# audiobackboard.net
KiCad netlist of a schematic drawn in EasyEDA
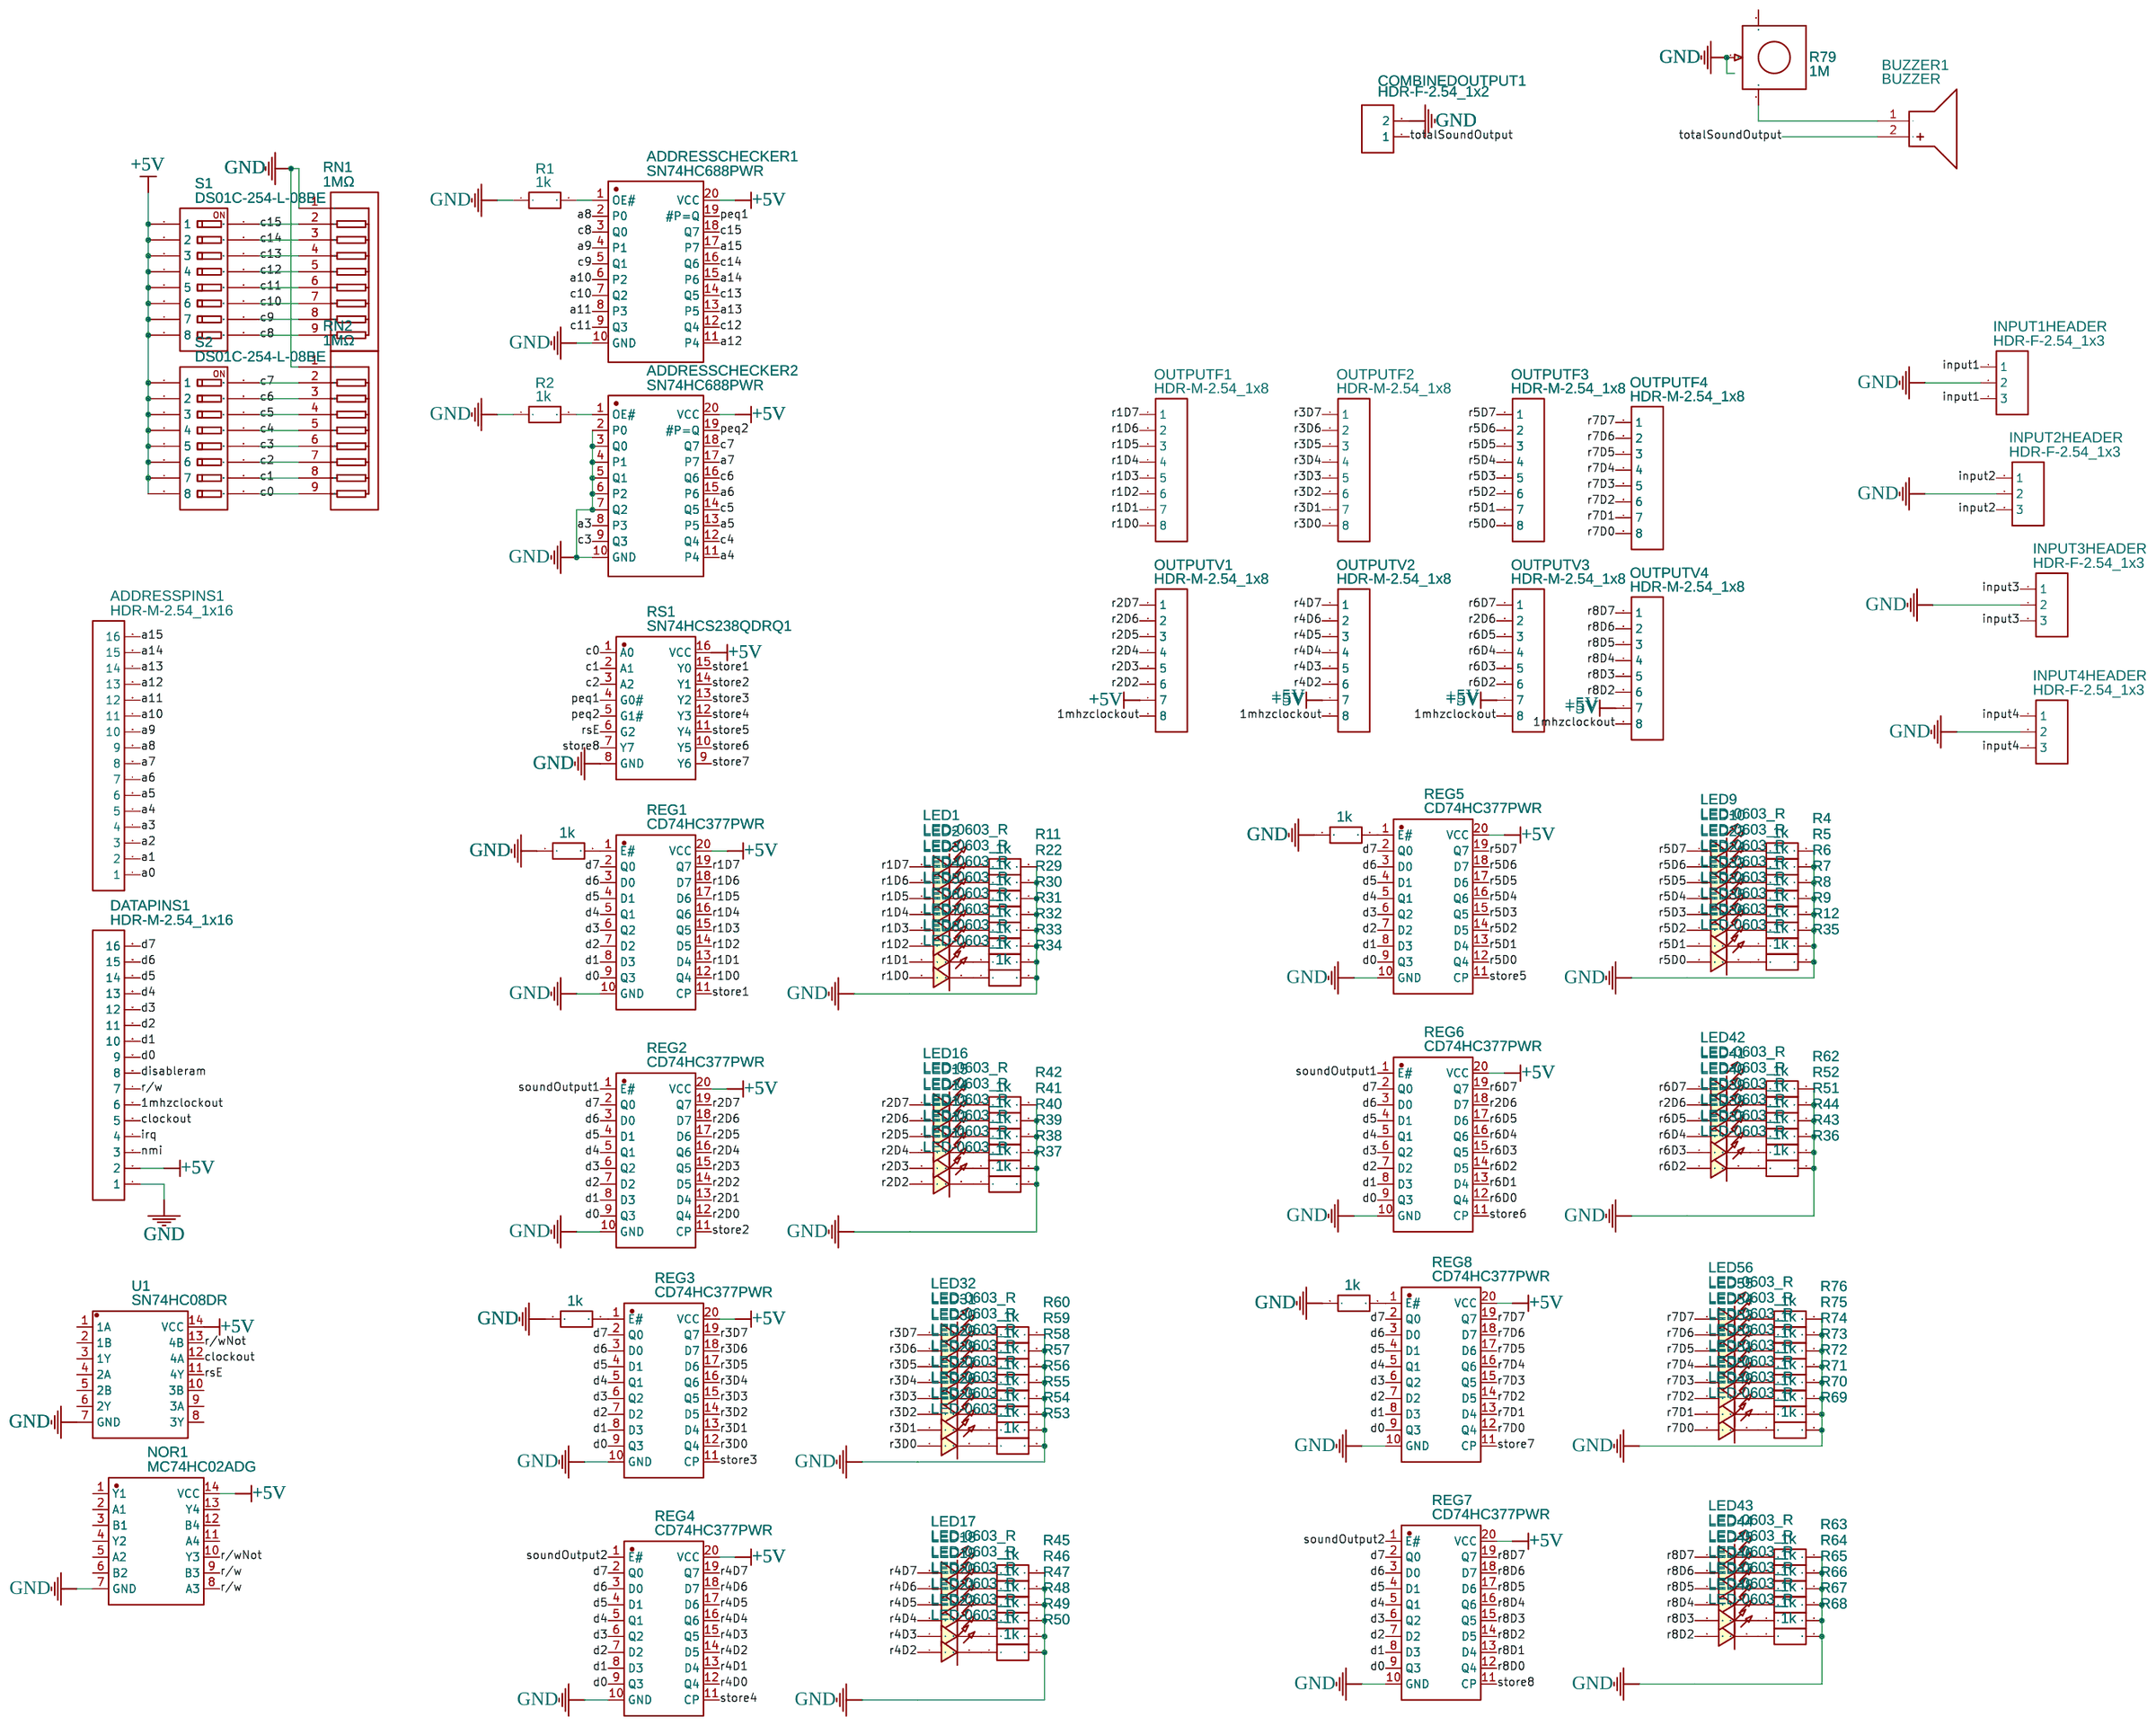
[diagram p0: schematic sheet]

(export (version "E")
  (design (tool "Eeschema 10.0.6"))
  (components
    (comp (ref "ADDRESSCHECKER1")
      (value "SN74HC688PWR")
      (fields (field (name "Manufacturer") "TI(德州仪器)"))
      (libsource (lib "") (part "SN74HC688PWR"))
    )
    (comp (ref "ADDRESSCHECKER2")
      (value "SN74HC688PWR")
      (fields (field (name "Manufacturer") "TI(德州仪器)"))
      (libsource (lib "") (part "SN74HC688PWR"))
    )
    (comp (ref "ADDRESSPINS1") (value "HDR-M-2.54_1x16") (libsource (lib "") (part "HDR-M-2.54_1x16_1")))
    (comp (ref "BUZZER1")
      (value "BUZZER")
      (fields (field (name "Manufacturer Part") "buzzer"))
      (libsource (lib "") (part "BUZZER"))
    )
    (comp (ref "COMBINEDOUTPUT1") (value "HDR-F-2.54_1x2") (libsource (lib "") (part "HDR-F-2.54_1x2")))
    (comp (ref "DATAPINS1") (value "HDR-M-2.54_1x16") (libsource (lib "") (part "HDR-M-2.54_1x16")))
    (comp (ref "INPUT1HEADER") (value "HDR-F-2.54_1x3") (libsource (lib "") (part "HDR-F-2.54_1x3")))
    (comp (ref "INPUT2HEADER") (value "HDR-F-2.54_1x3") (libsource (lib "") (part "HDR-F-2.54_1x3_2")))
    (comp (ref "INPUT3HEADER") (value "HDR-F-2.54_1x3") (libsource (lib "") (part "HDR-F-2.54_1x3_3")))
    (comp (ref "INPUT4HEADER") (value "HDR-F-2.54_1x3") (libsource (lib "") (part "HDR-F-2.54_1x3_1")))
    (comp (ref "LED1")
      (value "LED-0603_R")
      (fields
        (field (name "Manufacturer Part") "19-217/R6C-AL1M2VY/3T")
        (field (name "Manufacturer") "EVERLIGHT(台湾亿光)")
      )
      (libsource (lib "") (part "LED-0603_R"))
    )
    (comp (ref "LED2")
      (value "LED-0603_R")
      (fields
        (field (name "Manufacturer Part") "19-217/R6C-AL1M2VY/3T")
        (field (name "Manufacturer") "EVERLIGHT(台湾亿光)")
      )
      (libsource (lib "") (part "LED-0603_R"))
    )
    (comp (ref "LED3")
      (value "LED-0603_R")
      (fields
        (field (name "Manufacturer Part") "19-217/R6C-AL1M2VY/3T")
        (field (name "Manufacturer") "EVERLIGHT(台湾亿光)")
      )
      (libsource (lib "") (part "LED-0603_R"))
    )
    (comp (ref "LED4")
      (value "LED-0603_R")
      (fields
        (field (name "Manufacturer Part") "19-217/R6C-AL1M2VY/3T")
        (field (name "Manufacturer") "EVERLIGHT(台湾亿光)")
      )
      (libsource (lib "") (part "LED-0603_R"))
    )
    (comp (ref "LED5")
      (value "LED-0603_R")
      (fields
        (field (name "Manufacturer Part") "19-217/R6C-AL1M2VY/3T")
        (field (name "Manufacturer") "EVERLIGHT(台湾亿光)")
      )
      (libsource (lib "") (part "LED-0603_R"))
    )
    (comp (ref "LED6")
      (value "LED-0603_R")
      (fields
        (field (name "Manufacturer Part") "19-217/R6C-AL1M2VY/3T")
        (field (name "Manufacturer") "EVERLIGHT(台湾亿光)")
      )
      (libsource (lib "") (part "LED-0603_R"))
    )
    (comp (ref "LED7")
      (value "LED-0603_R")
      (fields
        (field (name "Manufacturer Part") "19-217/R6C-AL1M2VY/3T")
        (field (name "Manufacturer") "EVERLIGHT(台湾亿光)")
      )
      (libsource (lib "") (part "LED-0603_R"))
    )
    (comp (ref "LED8")
      (value "LED-0603_R")
      (fields
        (field (name "Manufacturer Part") "19-217/R6C-AL1M2VY/3T")
        (field (name "Manufacturer") "EVERLIGHT(台湾亿光)")
      )
      (libsource (lib "") (part "LED-0603_R"))
    )
    (comp (ref "LED9")
      (value "LED-0603_R")
      (fields
        (field (name "Manufacturer Part") "19-217/R6C-AL1M2VY/3T")
        (field (name "Manufacturer") "EVERLIGHT(台湾亿光)")
      )
      (libsource (lib "") (part "LED-0603_R"))
    )
    (comp (ref "LED10")
      (value "LED-0603_R")
      (fields
        (field (name "Manufacturer Part") "19-217/R6C-AL1M2VY/3T")
        (field (name "Manufacturer") "EVERLIGHT(台湾亿光)")
      )
      (libsource (lib "") (part "LED-0603_R"))
    )
    (comp (ref "LED11")
      (value "LED-0603_R")
      (fields
        (field (name "Manufacturer Part") "19-217/R6C-AL1M2VY/3T")
        (field (name "Manufacturer") "EVERLIGHT(台湾亿光)")
      )
      (libsource (lib "") (part "LED-0603_R"))
    )
    (comp (ref "LED12")
      (value "LED-0603_R")
      (fields
        (field (name "Manufacturer Part") "19-217/R6C-AL1M2VY/3T")
        (field (name "Manufacturer") "EVERLIGHT(台湾亿光)")
      )
      (libsource (lib "") (part "LED-0603_R"))
    )
    (comp (ref "LED13")
      (value "LED-0603_R")
      (fields
        (field (name "Manufacturer Part") "19-217/R6C-AL1M2VY/3T")
        (field (name "Manufacturer") "EVERLIGHT(台湾亿光)")
      )
      (libsource (lib "") (part "LED-0603_R"))
    )
    (comp (ref "LED14")
      (value "LED-0603_R")
      (fields
        (field (name "Manufacturer Part") "19-217/R6C-AL1M2VY/3T")
        (field (name "Manufacturer") "EVERLIGHT(台湾亿光)")
      )
      (libsource (lib "") (part "LED-0603_R"))
    )
    (comp (ref "LED15")
      (value "LED-0603_R")
      (fields
        (field (name "Manufacturer Part") "19-217/R6C-AL1M2VY/3T")
        (field (name "Manufacturer") "EVERLIGHT(台湾亿光)")
      )
      (libsource (lib "") (part "LED-0603_R"))
    )
    (comp (ref "LED16")
      (value "LED-0603_R")
      (fields
        (field (name "Manufacturer Part") "19-217/R6C-AL1M2VY/3T")
        (field (name "Manufacturer") "EVERLIGHT(台湾亿光)")
      )
      (libsource (lib "") (part "LED-0603_R"))
    )
    (comp (ref "LED17")
      (value "LED-0603_R")
      (fields
        (field (name "Manufacturer Part") "19-217/R6C-AL1M2VY/3T")
        (field (name "Manufacturer") "EVERLIGHT(台湾亿光)")
      )
      (libsource (lib "") (part "LED-0603_R"))
    )
    (comp (ref "LED18")
      (value "LED-0603_R")
      (fields
        (field (name "Manufacturer Part") "19-217/R6C-AL1M2VY/3T")
        (field (name "Manufacturer") "EVERLIGHT(台湾亿光)")
      )
      (libsource (lib "") (part "LED-0603_R"))
    )
    (comp (ref "LED19")
      (value "LED-0603_R")
      (fields
        (field (name "Manufacturer Part") "19-217/R6C-AL1M2VY/3T")
        (field (name "Manufacturer") "EVERLIGHT(台湾亿光)")
      )
      (libsource (lib "") (part "LED-0603_R"))
    )
    (comp (ref "LED20")
      (value "LED-0603_R")
      (fields
        (field (name "Manufacturer Part") "19-217/R6C-AL1M2VY/3T")
        (field (name "Manufacturer") "EVERLIGHT(台湾亿光)")
      )
      (libsource (lib "") (part "LED-0603_R"))
    )
    (comp (ref "LED21")
      (value "LED-0603_R")
      (fields
        (field (name "Manufacturer Part") "19-217/R6C-AL1M2VY/3T")
        (field (name "Manufacturer") "EVERLIGHT(台湾亿光)")
      )
      (libsource (lib "") (part "LED-0603_R"))
    )
    (comp (ref "LED22")
      (value "LED-0603_R")
      (fields
        (field (name "Manufacturer Part") "19-217/R6C-AL1M2VY/3T")
        (field (name "Manufacturer") "EVERLIGHT(台湾亿光)")
      )
      (libsource (lib "") (part "LED-0603_R"))
    )
    (comp (ref "LED23")
      (value "LED-0603_R")
      (fields
        (field (name "Manufacturer Part") "19-217/R6C-AL1M2VY/3T")
        (field (name "Manufacturer") "EVERLIGHT(台湾亿光)")
      )
      (libsource (lib "") (part "LED-0603_R"))
    )
    (comp (ref "LED24")
      (value "LED-0603_R")
      (fields
        (field (name "Manufacturer Part") "19-217/R6C-AL1M2VY/3T")
        (field (name "Manufacturer") "EVERLIGHT(台湾亿光)")
      )
      (libsource (lib "") (part "LED-0603_R"))
    )
    (comp (ref "LED25")
      (value "LED-0603_R")
      (fields
        (field (name "Manufacturer Part") "19-217/R6C-AL1M2VY/3T")
        (field (name "Manufacturer") "EVERLIGHT(台湾亿光)")
      )
      (libsource (lib "") (part "LED-0603_R"))
    )
    (comp (ref "LED26")
      (value "LED-0603_R")
      (fields
        (field (name "Manufacturer Part") "19-217/R6C-AL1M2VY/3T")
        (field (name "Manufacturer") "EVERLIGHT(台湾亿光)")
      )
      (libsource (lib "") (part "LED-0603_R"))
    )
    (comp (ref "LED27")
      (value "LED-0603_R")
      (fields
        (field (name "Manufacturer Part") "19-217/R6C-AL1M2VY/3T")
        (field (name "Manufacturer") "EVERLIGHT(台湾亿光)")
      )
      (libsource (lib "") (part "LED-0603_R"))
    )
    (comp (ref "LED28")
      (value "LED-0603_R")
      (fields
        (field (name "Manufacturer Part") "19-217/R6C-AL1M2VY/3T")
        (field (name "Manufacturer") "EVERLIGHT(台湾亿光)")
      )
      (libsource (lib "") (part "LED-0603_R"))
    )
    (comp (ref "LED29")
      (value "LED-0603_R")
      (fields
        (field (name "Manufacturer Part") "19-217/R6C-AL1M2VY/3T")
        (field (name "Manufacturer") "EVERLIGHT(台湾亿光)")
      )
      (libsource (lib "") (part "LED-0603_R"))
    )
    (comp (ref "LED30")
      (value "LED-0603_R")
      (fields
        (field (name "Manufacturer Part") "19-217/R6C-AL1M2VY/3T")
        (field (name "Manufacturer") "EVERLIGHT(台湾亿光)")
      )
      (libsource (lib "") (part "LED-0603_R"))
    )
    (comp (ref "LED31")
      (value "LED-0603_R")
      (fields
        (field (name "Manufacturer Part") "19-217/R6C-AL1M2VY/3T")
        (field (name "Manufacturer") "EVERLIGHT(台湾亿光)")
      )
      (libsource (lib "") (part "LED-0603_R"))
    )
    (comp (ref "LED32")
      (value "LED-0603_R")
      (fields
        (field (name "Manufacturer Part") "19-217/R6C-AL1M2VY/3T")
        (field (name "Manufacturer") "EVERLIGHT(台湾亿光)")
      )
      (libsource (lib "") (part "LED-0603_R"))
    )
    (comp (ref "LED33")
      (value "LED-0603_R")
      (fields
        (field (name "Manufacturer Part") "19-217/R6C-AL1M2VY/3T")
        (field (name "Manufacturer") "EVERLIGHT(台湾亿光)")
      )
      (libsource (lib "") (part "LED-0603_R"))
    )
    (comp (ref "LED34")
      (value "LED-0603_R")
      (fields
        (field (name "Manufacturer Part") "19-217/R6C-AL1M2VY/3T")
        (field (name "Manufacturer") "EVERLIGHT(台湾亿光)")
      )
      (libsource (lib "") (part "LED-0603_R"))
    )
    (comp (ref "LED35")
      (value "LED-0603_R")
      (fields
        (field (name "Manufacturer Part") "19-217/R6C-AL1M2VY/3T")
        (field (name "Manufacturer") "EVERLIGHT(台湾亿光)")
      )
      (libsource (lib "") (part "LED-0603_R"))
    )
    (comp (ref "LED36")
      (value "LED-0603_R")
      (fields
        (field (name "Manufacturer Part") "19-217/R6C-AL1M2VY/3T")
        (field (name "Manufacturer") "EVERLIGHT(台湾亿光)")
      )
      (libsource (lib "") (part "LED-0603_R"))
    )
    (comp (ref "LED37")
      (value "LED-0603_R")
      (fields
        (field (name "Manufacturer Part") "19-217/R6C-AL1M2VY/3T")
        (field (name "Manufacturer") "EVERLIGHT(台湾亿光)")
      )
      (libsource (lib "") (part "LED-0603_R"))
    )
    (comp (ref "LED38")
      (value "LED-0603_R")
      (fields
        (field (name "Manufacturer Part") "19-217/R6C-AL1M2VY/3T")
        (field (name "Manufacturer") "EVERLIGHT(台湾亿光)")
      )
      (libsource (lib "") (part "LED-0603_R"))
    )
    (comp (ref "LED39")
      (value "LED-0603_R")
      (fields
        (field (name "Manufacturer Part") "19-217/R6C-AL1M2VY/3T")
        (field (name "Manufacturer") "EVERLIGHT(台湾亿光)")
      )
      (libsource (lib "") (part "LED-0603_R"))
    )
    (comp (ref "LED40")
      (value "LED-0603_R")
      (fields
        (field (name "Manufacturer Part") "19-217/R6C-AL1M2VY/3T")
        (field (name "Manufacturer") "EVERLIGHT(台湾亿光)")
      )
      (libsource (lib "") (part "LED-0603_R"))
    )
    (comp (ref "LED41")
      (value "LED-0603_R")
      (fields
        (field (name "Manufacturer Part") "19-217/R6C-AL1M2VY/3T")
        (field (name "Manufacturer") "EVERLIGHT(台湾亿光)")
      )
      (libsource (lib "") (part "LED-0603_R"))
    )
    (comp (ref "LED42")
      (value "LED-0603_R")
      (fields
        (field (name "Manufacturer Part") "19-217/R6C-AL1M2VY/3T")
        (field (name "Manufacturer") "EVERLIGHT(台湾亿光)")
      )
      (libsource (lib "") (part "LED-0603_R"))
    )
    (comp (ref "LED43")
      (value "LED-0603_R")
      (fields
        (field (name "Manufacturer Part") "19-217/R6C-AL1M2VY/3T")
        (field (name "Manufacturer") "EVERLIGHT(台湾亿光)")
      )
      (libsource (lib "") (part "LED-0603_R"))
    )
    (comp (ref "LED44")
      (value "LED-0603_R")
      (fields
        (field (name "Manufacturer Part") "19-217/R6C-AL1M2VY/3T")
        (field (name "Manufacturer") "EVERLIGHT(台湾亿光)")
      )
      (libsource (lib "") (part "LED-0603_R"))
    )
    (comp (ref "LED45")
      (value "LED-0603_R")
      (fields
        (field (name "Manufacturer Part") "19-217/R6C-AL1M2VY/3T")
        (field (name "Manufacturer") "EVERLIGHT(台湾亿光)")
      )
      (libsource (lib "") (part "LED-0603_R"))
    )
    (comp (ref "LED46")
      (value "LED-0603_R")
      (fields
        (field (name "Manufacturer Part") "19-217/R6C-AL1M2VY/3T")
        (field (name "Manufacturer") "EVERLIGHT(台湾亿光)")
      )
      (libsource (lib "") (part "LED-0603_R"))
    )
    (comp (ref "LED47")
      (value "LED-0603_R")
      (fields
        (field (name "Manufacturer Part") "19-217/R6C-AL1M2VY/3T")
        (field (name "Manufacturer") "EVERLIGHT(台湾亿光)")
      )
      (libsource (lib "") (part "LED-0603_R"))
    )
    (comp (ref "LED48")
      (value "LED-0603_R")
      (fields
        (field (name "Manufacturer Part") "19-217/R6C-AL1M2VY/3T")
        (field (name "Manufacturer") "EVERLIGHT(台湾亿光)")
      )
      (libsource (lib "") (part "LED-0603_R"))
    )
    (comp (ref "LED49")
      (value "LED-0603_R")
      (fields
        (field (name "Manufacturer Part") "19-217/R6C-AL1M2VY/3T")
        (field (name "Manufacturer") "EVERLIGHT(台湾亿光)")
      )
      (libsource (lib "") (part "LED-0603_R"))
    )
    (comp (ref "LED50")
      (value "LED-0603_R")
      (fields
        (field (name "Manufacturer Part") "19-217/R6C-AL1M2VY/3T")
        (field (name "Manufacturer") "EVERLIGHT(台湾亿光)")
      )
      (libsource (lib "") (part "LED-0603_R"))
    )
    (comp (ref "LED51")
      (value "LED-0603_R")
      (fields
        (field (name "Manufacturer Part") "19-217/R6C-AL1M2VY/3T")
        (field (name "Manufacturer") "EVERLIGHT(台湾亿光)")
      )
      (libsource (lib "") (part "LED-0603_R"))
    )
    (comp (ref "LED52")
      (value "LED-0603_R")
      (fields
        (field (name "Manufacturer Part") "19-217/R6C-AL1M2VY/3T")
        (field (name "Manufacturer") "EVERLIGHT(台湾亿光)")
      )
      (libsource (lib "") (part "LED-0603_R"))
    )
    (comp (ref "LED53")
      (value "LED-0603_R")
      (fields
        (field (name "Manufacturer Part") "19-217/R6C-AL1M2VY/3T")
        (field (name "Manufacturer") "EVERLIGHT(台湾亿光)")
      )
      (libsource (lib "") (part "LED-0603_R"))
    )
    (comp (ref "LED54")
      (value "LED-0603_R")
      (fields
        (field (name "Manufacturer Part") "19-217/R6C-AL1M2VY/3T")
        (field (name "Manufacturer") "EVERLIGHT(台湾亿光)")
      )
      (libsource (lib "") (part "LED-0603_R"))
    )
    (comp (ref "LED55")
      (value "LED-0603_R")
      (fields
        (field (name "Manufacturer Part") "19-217/R6C-AL1M2VY/3T")
        (field (name "Manufacturer") "EVERLIGHT(台湾亿光)")
      )
      (libsource (lib "") (part "LED-0603_R"))
    )
    (comp (ref "LED56")
      (value "LED-0603_R")
      (fields
        (field (name "Manufacturer Part") "19-217/R6C-AL1M2VY/3T")
        (field (name "Manufacturer") "EVERLIGHT(台湾亿光)")
      )
      (libsource (lib "") (part "LED-0603_R"))
    )
    (comp (ref "NOR1")
      (value "MC74HC02ADG")
      (fields (field (name "Manufacturer") "onsemi(安森美)"))
      (libsource (lib "") (part "MC74HC02ADG"))
    )
    (comp (ref "OUTPUTF1") (value "HDR-M-2.54_1x8") (libsource (lib "") (part "HDR-M-2.54_1x8_1")))
    (comp (ref "OUTPUTF2") (value "HDR-M-2.54_1x8") (libsource (lib "") (part "HDR-M-2.54_1x8_1")))
    (comp (ref "OUTPUTF3") (value "HDR-M-2.54_1x8") (libsource (lib "") (part "HDR-M-2.54_1x8_1")))
    (comp (ref "OUTPUTF4") (value "HDR-M-2.54_1x8") (libsource (lib "") (part "HDR-M-2.54_1x8_1")))
    (comp (ref "OUTPUTV1") (value "HDR-M-2.54_1x8") (libsource (lib "") (part "HDR-M-2.54_1x8")))
    (comp (ref "OUTPUTV2") (value "HDR-M-2.54_1x8") (libsource (lib "") (part "HDR-M-2.54_1x8")))
    (comp (ref "OUTPUTV3") (value "HDR-M-2.54_1x8") (libsource (lib "") (part "HDR-M-2.54_1x8")))
    (comp (ref "OUTPUTV4") (value "HDR-M-2.54_1x8") (libsource (lib "") (part "HDR-M-2.54_1x8")))
    (comp (ref "R1") (value "1k") (libsource (lib "") (part "R_1206_EU")))
    (comp (ref "R2") (value "1k") (libsource (lib "") (part "R_1206_EU")))
    (comp (ref "R3") (value "1k") (libsource (lib "") (part "R_1206_EU")))
    (comp (ref "R4") (value "1k") (libsource (lib "") (part "R_1206_EU")))
    (comp (ref "R5") (value "1k") (libsource (lib "") (part "R_1206_EU")))
    (comp (ref "R6") (value "1k") (libsource (lib "") (part "R_1206_EU")))
    (comp (ref "R7") (value "1k") (libsource (lib "") (part "R_1206_EU")))
    (comp (ref "R8") (value "1k") (libsource (lib "") (part "R_1206_EU")))
    (comp (ref "R9") (value "1k") (libsource (lib "") (part "R_1206_EU")))
    (comp (ref "R11") (value "1k") (libsource (lib "") (part "R_1206_EU")))
    (comp (ref "R12") (value "1k") (libsource (lib "") (part "R_1206_EU")))
    (comp (ref "R22") (value "1k") (libsource (lib "") (part "R_1206_EU")))
    (comp (ref "R29") (value "1k") (libsource (lib "") (part "R_1206_EU")))
    (comp (ref "R30") (value "1k") (libsource (lib "") (part "R_1206_EU")))
    (comp (ref "R31") (value "1k") (libsource (lib "") (part "R_1206_EU")))
    (comp (ref "R32") (value "1k") (libsource (lib "") (part "R_1206_EU")))
    (comp (ref "R33") (value "1k") (libsource (lib "") (part "R_1206_EU")))
    (comp (ref "R34") (value "1k") (libsource (lib "") (part "R_1206_EU")))
    (comp (ref "R35") (value "1k") (libsource (lib "") (part "R_1206_EU")))
    (comp (ref "R36") (value "1k") (libsource (lib "") (part "R_1206_EU")))
    (comp (ref "R37") (value "1k") (libsource (lib "") (part "R_1206_EU")))
    (comp (ref "R38") (value "1k") (libsource (lib "") (part "R_1206_EU")))
    (comp (ref "R39") (value "1k") (libsource (lib "") (part "R_1206_EU")))
    (comp (ref "R40") (value "1k") (libsource (lib "") (part "R_1206_EU")))
    (comp (ref "R41") (value "1k") (libsource (lib "") (part "R_1206_EU")))
    (comp (ref "R42") (value "1k") (libsource (lib "") (part "R_1206_EU")))
    (comp (ref "R43") (value "1k") (libsource (lib "") (part "R_1206_EU")))
    (comp (ref "R44") (value "1k") (libsource (lib "") (part "R_1206_EU")))
    (comp (ref "R45") (value "1k") (libsource (lib "") (part "R_1206_EU")))
    (comp (ref "R46") (value "1k") (libsource (lib "") (part "R_1206_EU")))
    (comp (ref "R47") (value "1k") (libsource (lib "") (part "R_1206_EU")))
    (comp (ref "R48") (value "1k") (libsource (lib "") (part "R_1206_EU")))
    (comp (ref "R49") (value "1k") (libsource (lib "") (part "R_1206_EU")))
    (comp (ref "R50") (value "1k") (libsource (lib "") (part "R_1206_EU")))
    (comp (ref "R51") (value "1k") (libsource (lib "") (part "R_1206_EU")))
    (comp (ref "R52") (value "1k") (libsource (lib "") (part "R_1206_EU")))
    (comp (ref "R53") (value "1k") (libsource (lib "") (part "R_1206_EU")))
    (comp (ref "R54") (value "1k") (libsource (lib "") (part "R_1206_EU")))
    (comp (ref "R55") (value "1k") (libsource (lib "") (part "R_1206_EU")))
    (comp (ref "R56") (value "1k") (libsource (lib "") (part "R_1206_EU")))
    (comp (ref "R57") (value "1k") (libsource (lib "") (part "R_1206_EU")))
    (comp (ref "R58") (value "1k") (libsource (lib "") (part "R_1206_EU")))
    (comp (ref "R59") (value "1k") (libsource (lib "") (part "R_1206_EU")))
    (comp (ref "R60") (value "1k") (libsource (lib "") (part "R_1206_EU")))
    (comp (ref "R61") (value "1k") (libsource (lib "") (part "R_1206_EU")))
    (comp (ref "R62") (value "1k") (libsource (lib "") (part "R_1206_EU")))
    (comp (ref "R63") (value "1k") (libsource (lib "") (part "R_1206_EU")))
    (comp (ref "R64") (value "1k") (libsource (lib "") (part "R_1206_EU")))
    (comp (ref "R65") (value "1k") (libsource (lib "") (part "R_1206_EU")))
    (comp (ref "R66") (value "1k") (libsource (lib "") (part "R_1206_EU")))
    (comp (ref "R67") (value "1k") (libsource (lib "") (part "R_1206_EU")))
    (comp (ref "R68") (value "1k") (libsource (lib "") (part "R_1206_EU")))
    (comp (ref "R69") (value "1k") (libsource (lib "") (part "R_1206_EU")))
    (comp (ref "R70") (value "1k") (libsource (lib "") (part "R_1206_EU")))
    (comp (ref "R71") (value "1k") (libsource (lib "") (part "R_1206_EU")))
    (comp (ref "R72") (value "1k") (libsource (lib "") (part "R_1206_EU")))
    (comp (ref "R73") (value "1k") (libsource (lib "") (part "R_1206_EU")))
    (comp (ref "R74") (value "1k") (libsource (lib "") (part "R_1206_EU")))
    (comp (ref "R75") (value "1k") (libsource (lib "") (part "R_1206_EU")))
    (comp (ref "R76") (value "1k") (libsource (lib "") (part "R_1206_EU")))
    (comp (ref "R77") (value "1k") (libsource (lib "") (part "R_1206_EU")))
    (comp (ref "R78") (value "1k") (libsource (lib "") (part "R_1206_EU")))
    (comp (ref "R79")
      (value "1M")
      (fields
        (field (name "Manufacturer Part") "3386T-1-LS1MEG(105)")
        (field (name "Manufacturer") "Jameco ValuePro")
      )
      (libsource (lib "") (part "3/8 Inch Square Cermet Potentiometer 1MEG Ohms 1/2 Watt 1 Turn Thru Hole"))
    )
    (comp (ref "REG1")
      (value "CD74HC377PWR")
      (fields (field (name "Manufacturer") "TI(德州仪器)"))
      (libsource (lib "") (part "CD74HC377PWR"))
    )
    (comp (ref "REG2")
      (value "CD74HC377PWR")
      (fields (field (name "Manufacturer") "TI(德州仪器)"))
      (libsource (lib "") (part "CD74HC377PWR"))
    )
    (comp (ref "REG3")
      (value "CD74HC377PWR")
      (fields (field (name "Manufacturer") "TI(德州仪器)"))
      (libsource (lib "") (part "CD74HC377PWR"))
    )
    (comp (ref "REG4")
      (value "CD74HC377PWR")
      (fields (field (name "Manufacturer") "TI(德州仪器)"))
      (libsource (lib "") (part "CD74HC377PWR"))
    )
    (comp (ref "REG5")
      (value "CD74HC377PWR")
      (fields (field (name "Manufacturer") "TI(德州仪器)"))
      (libsource (lib "") (part "CD74HC377PWR"))
    )
    (comp (ref "REG6")
      (value "CD74HC377PWR")
      (fields (field (name "Manufacturer") "TI(德州仪器)"))
      (libsource (lib "") (part "CD74HC377PWR"))
    )
    (comp (ref "REG7")
      (value "CD74HC377PWR")
      (fields (field (name "Manufacturer") "TI(德州仪器)"))
      (libsource (lib "") (part "CD74HC377PWR"))
    )
    (comp (ref "REG8")
      (value "CD74HC377PWR")
      (fields (field (name "Manufacturer") "TI(德州仪器)"))
      (libsource (lib "") (part "CD74HC377PWR"))
    )
    (comp (ref "RN1")
      (value "1MΩ")
      (fields (field (name "Manufacturer Part") "4609X-101-105LF") (field (name "Manufacturer") "BOURNS"))
      (libsource (lib "") (part "4609X-101-105LF"))
    )
    (comp (ref "RN2")
      (value "1MΩ")
      (fields (field (name "Manufacturer Part") "4609X-101-105LF") (field (name "Manufacturer") "BOURNS"))
      (libsource (lib "") (part "4609X-101-105LF"))
    )
    (comp (ref "RS1")
      (value "SN74HCS238QDRQ1")
      (fields (field (name "Manufacturer") "TI(德州仪器)"))
      (libsource (lib "") (part "SN74HCS238QDRQ1"))
    )
    (comp (ref "S1")
      (value "DS01C-254-L-08BE")
      (fields
        (field (name "Manufacturer Part") "DS01C-254-L-07BE")
        (field (name "Manufacturer") "CUI Devices")
      )
      (libsource (lib "") (part "DS01C-254-L-08BE"))
    )
    (comp (ref "S2")
      (value "DS01C-254-L-08BE")
      (fields
        (field (name "Manufacturer Part") "DS01C-254-L-07BE")
        (field (name "Manufacturer") "CUI Devices")
      )
      (libsource (lib "") (part "DS01C-254-L-08BE"))
    )
    (comp (ref "U1")
      (value "SN74HC08DR")
      (fields (field (name "Manufacturer") "TI(德州仪器)"))
      (libsource (lib "") (part "SN74HC08DR"))
    )
  )
  (nets
    (net (code "1") (name "+5V") (class "Default")
      (node (ref "ADDRESSCHECKER1") (pin "20") (pinfunction "VCC_20") (pintype "unspecified"))
      (node (ref "ADDRESSCHECKER2") (pin "20") (pinfunction "VCC_20") (pintype "unspecified"))
      (node (ref "DATAPINS1") (pin "2") (pinfunction "2_2") (pintype "unspecified"))
      (node (ref "NOR1") (pin "14") (pinfunction "VCC_14") (pintype "unspecified"))
      (node (ref "OUTPUTV1") (pin "7") (pinfunction "7_7") (pintype "unspecified"))
      (node (ref "OUTPUTV2") (pin "7") (pinfunction "7_7") (pintype "unspecified"))
      (node (ref "OUTPUTV3") (pin "7") (pinfunction "7_7") (pintype "unspecified"))
      (node (ref "OUTPUTV4") (pin "7") (pinfunction "7_7") (pintype "unspecified"))
      (node (ref "REG1") (pin "20") (pinfunction "VCC_20") (pintype "unspecified"))
      (node (ref "REG2") (pin "20") (pinfunction "VCC_20") (pintype "unspecified"))
      (node (ref "REG3") (pin "20") (pinfunction "VCC_20") (pintype "unspecified"))
      (node (ref "REG4") (pin "20") (pinfunction "VCC_20") (pintype "unspecified"))
      (node (ref "REG5") (pin "20") (pinfunction "VCC_20") (pintype "unspecified"))
      (node (ref "REG6") (pin "20") (pinfunction "VCC_20") (pintype "unspecified"))
      (node (ref "REG7") (pin "20") (pinfunction "VCC_20") (pintype "unspecified"))
      (node (ref "REG8") (pin "20") (pinfunction "VCC_20") (pintype "unspecified"))
      (node (ref "RS1") (pin "16") (pinfunction "VCC_16") (pintype "unspecified"))
      (node (ref "S1") (pin "1") (pinfunction "1_1") (pintype "unspecified"))
      (node (ref "S1") (pin "2") (pinfunction "2_2") (pintype "unspecified"))
      (node (ref "S1") (pin "3") (pinfunction "3_3") (pintype "unspecified"))
      (node (ref "S1") (pin "4") (pinfunction "4_4") (pintype "unspecified"))
      (node (ref "S1") (pin "5") (pinfunction "5_5") (pintype "unspecified"))
      (node (ref "S1") (pin "6") (pinfunction "6_6") (pintype "unspecified"))
      (node (ref "S1") (pin "7") (pinfunction "7_7") (pintype "unspecified"))
      (node (ref "S1") (pin "8") (pinfunction "8_8") (pintype "unspecified"))
      (node (ref "S2") (pin "1") (pinfunction "1_1") (pintype "unspecified"))
      (node (ref "S2") (pin "2") (pinfunction "2_2") (pintype "unspecified"))
      (node (ref "S2") (pin "3") (pinfunction "3_3") (pintype "unspecified"))
      (node (ref "S2") (pin "4") (pinfunction "4_4") (pintype "unspecified"))
      (node (ref "S2") (pin "5") (pinfunction "5_5") (pintype "unspecified"))
      (node (ref "S2") (pin "6") (pinfunction "6_6") (pintype "unspecified"))
      (node (ref "S2") (pin "7") (pinfunction "7_7") (pintype "unspecified"))
      (node (ref "S2") (pin "8") (pinfunction "8_8") (pintype "unspecified"))
      (node (ref "U1") (pin "14") (pinfunction "VCC_14") (pintype "unspecified"))
    )
    (net (code "2") (name "/1mhzclockout") (class "Default")
      (node (ref "DATAPINS1") (pin "6") (pinfunction "6_6") (pintype "unspecified"))
      (node (ref "OUTPUTV1") (pin "8") (pinfunction "8_8") (pintype "unspecified"))
      (node (ref "OUTPUTV2") (pin "8") (pinfunction "8_8") (pintype "unspecified"))
      (node (ref "OUTPUTV3") (pin "8") (pinfunction "8_8") (pintype "unspecified"))
      (node (ref "OUTPUTV4") (pin "8") (pinfunction "8_8") (pintype "unspecified"))
    )
    (net (code "3") (name "/a0") (class "Default")
      (node (ref "ADDRESSPINS1") (pin "1") (pinfunction "1_1") (pintype "unspecified"))
    )
    (net (code "4") (name "/a1") (class "Default")
      (node (ref "ADDRESSPINS1") (pin "2") (pinfunction "2_2") (pintype "unspecified"))
    )
    (net (code "5") (name "/a2") (class "Default")
      (node (ref "ADDRESSPINS1") (pin "3") (pinfunction "3_3") (pintype "unspecified"))
    )
    (net (code "6") (name "/a3") (class "Default")
      (node (ref "ADDRESSCHECKER2") (pin "8") (pinfunction "P3_8") (pintype "unspecified"))
      (node (ref "ADDRESSPINS1") (pin "4") (pinfunction "4_4") (pintype "unspecified"))
    )
    (net (code "7") (name "/a4") (class "Default")
      (node (ref "ADDRESSCHECKER2") (pin "11") (pinfunction "P4_11") (pintype "unspecified"))
      (node (ref "ADDRESSPINS1") (pin "5") (pinfunction "5_5") (pintype "unspecified"))
    )
    (net (code "8") (name "/a5") (class "Default")
      (node (ref "ADDRESSCHECKER2") (pin "13") (pinfunction "P5_13") (pintype "unspecified"))
      (node (ref "ADDRESSPINS1") (pin "6") (pinfunction "6_6") (pintype "unspecified"))
    )
    (net (code "9") (name "/a6") (class "Default")
      (node (ref "ADDRESSCHECKER2") (pin "15") (pinfunction "P6_15") (pintype "unspecified"))
      (node (ref "ADDRESSPINS1") (pin "7") (pinfunction "7_7") (pintype "unspecified"))
    )
    (net (code "10") (name "/a7") (class "Default")
      (node (ref "ADDRESSCHECKER2") (pin "17") (pinfunction "P7_17") (pintype "unspecified"))
      (node (ref "ADDRESSPINS1") (pin "8") (pinfunction "8_8") (pintype "unspecified"))
    )
    (net (code "11") (name "/a8") (class "Default")
      (node (ref "ADDRESSCHECKER1") (pin "2") (pinfunction "P0_2") (pintype "unspecified"))
      (node (ref "ADDRESSPINS1") (pin "9") (pinfunction "9_9") (pintype "unspecified"))
    )
    (net (code "12") (name "/a9") (class "Default")
      (node (ref "ADDRESSCHECKER1") (pin "4") (pinfunction "P1_4") (pintype "unspecified"))
      (node (ref "ADDRESSPINS1") (pin "10") (pinfunction "10_10") (pintype "unspecified"))
    )
    (net (code "13") (name "/a10") (class "Default")
      (node (ref "ADDRESSCHECKER1") (pin "6") (pinfunction "P2_6") (pintype "unspecified"))
      (node (ref "ADDRESSPINS1") (pin "11") (pinfunction "11_11") (pintype "unspecified"))
    )
    (net (code "14") (name "/a11") (class "Default")
      (node (ref "ADDRESSCHECKER1") (pin "8") (pinfunction "P3_8") (pintype "unspecified"))
      (node (ref "ADDRESSPINS1") (pin "12") (pinfunction "12_12") (pintype "unspecified"))
    )
    (net (code "15") (name "/a12") (class "Default")
      (node (ref "ADDRESSCHECKER1") (pin "11") (pinfunction "P4_11") (pintype "unspecified"))
      (node (ref "ADDRESSPINS1") (pin "13") (pinfunction "13_13") (pintype "unspecified"))
    )
    (net (code "16") (name "/a13") (class "Default")
      (node (ref "ADDRESSCHECKER1") (pin "13") (pinfunction "P5_13") (pintype "unspecified"))
      (node (ref "ADDRESSPINS1") (pin "14") (pinfunction "14_14") (pintype "unspecified"))
    )
    (net (code "17") (name "/a14") (class "Default")
      (node (ref "ADDRESSCHECKER1") (pin "15") (pinfunction "P6_15") (pintype "unspecified"))
      (node (ref "ADDRESSPINS1") (pin "15") (pinfunction "15_15") (pintype "unspecified"))
    )
    (net (code "18") (name "/a15") (class "Default")
      (node (ref "ADDRESSCHECKER1") (pin "17") (pinfunction "P7_17") (pintype "unspecified"))
      (node (ref "ADDRESSPINS1") (pin "16") (pinfunction "16_16") (pintype "unspecified"))
    )
    (net (code "19") (name "/c0") (class "Default")
      (node (ref "RN2") (pin "9") (pinfunction "9_9") (pintype "input"))
      (node (ref "RS1") (pin "1") (pinfunction "A0_1") (pintype "unspecified"))
      (node (ref "S2") (pin "9") (pinfunction "9_9") (pintype "unspecified"))
    )
    (net (code "20") (name "/c1") (class "Default")
      (node (ref "RN2") (pin "8") (pinfunction "8_8") (pintype "input"))
      (node (ref "RS1") (pin "2") (pinfunction "A1_2") (pintype "unspecified"))
      (node (ref "S2") (pin "10") (pinfunction "10_10") (pintype "unspecified"))
    )
    (net (code "21") (name "/c2") (class "Default")
      (node (ref "RN2") (pin "7") (pinfunction "7_7") (pintype "input"))
      (node (ref "RS1") (pin "3") (pinfunction "A2_3") (pintype "unspecified"))
      (node (ref "S2") (pin "11") (pinfunction "11_11") (pintype "unspecified"))
    )
    (net (code "22") (name "/c3") (class "Default")
      (node (ref "ADDRESSCHECKER2") (pin "9") (pinfunction "Q3_9") (pintype "unspecified"))
      (node (ref "RN2") (pin "6") (pinfunction "6_6") (pintype "input"))
      (node (ref "S2") (pin "12") (pinfunction "12_12") (pintype "unspecified"))
    )
    (net (code "23") (name "/c4") (class "Default")
      (node (ref "ADDRESSCHECKER2") (pin "12") (pinfunction "Q4_12") (pintype "unspecified"))
      (node (ref "RN2") (pin "5") (pinfunction "5_5") (pintype "input"))
      (node (ref "S2") (pin "13") (pinfunction "13_13") (pintype "unspecified"))
    )
    (net (code "24") (name "/c5") (class "Default")
      (node (ref "ADDRESSCHECKER2") (pin "14") (pinfunction "Q5_14") (pintype "unspecified"))
      (node (ref "RN2") (pin "4") (pinfunction "4_4") (pintype "input"))
      (node (ref "S2") (pin "14") (pinfunction "14_14") (pintype "unspecified"))
    )
    (net (code "25") (name "/c6") (class "Default")
      (node (ref "ADDRESSCHECKER2") (pin "16") (pinfunction "Q6_16") (pintype "unspecified"))
      (node (ref "RN2") (pin "3") (pinfunction "3_3") (pintype "input"))
      (node (ref "S2") (pin "15") (pinfunction "15_15") (pintype "unspecified"))
    )
    (net (code "26") (name "/c7") (class "Default")
      (node (ref "ADDRESSCHECKER2") (pin "18") (pinfunction "Q7_18") (pintype "unspecified"))
      (node (ref "RN2") (pin "2") (pinfunction "2_2") (pintype "input"))
      (node (ref "S2") (pin "16") (pinfunction "16_16") (pintype "unspecified"))
    )
    (net (code "27") (name "/c8") (class "Default")
      (node (ref "ADDRESSCHECKER1") (pin "3") (pinfunction "Q0_3") (pintype "unspecified"))
      (node (ref "RN1") (pin "9") (pinfunction "9_9") (pintype "input"))
      (node (ref "S1") (pin "9") (pinfunction "9_9") (pintype "unspecified"))
    )
    (net (code "28") (name "/c9") (class "Default")
      (node (ref "ADDRESSCHECKER1") (pin "5") (pinfunction "Q1_5") (pintype "unspecified"))
      (node (ref "RN1") (pin "8") (pinfunction "8_8") (pintype "input"))
      (node (ref "S1") (pin "10") (pinfunction "10_10") (pintype "unspecified"))
    )
    (net (code "29") (name "/c10") (class "Default")
      (node (ref "ADDRESSCHECKER1") (pin "7") (pinfunction "Q2_7") (pintype "unspecified"))
      (node (ref "RN1") (pin "7") (pinfunction "7_7") (pintype "input"))
      (node (ref "S1") (pin "11") (pinfunction "11_11") (pintype "unspecified"))
    )
    (net (code "30") (name "/c11") (class "Default")
      (node (ref "ADDRESSCHECKER1") (pin "9") (pinfunction "Q3_9") (pintype "unspecified"))
      (node (ref "RN1") (pin "6") (pinfunction "6_6") (pintype "input"))
      (node (ref "S1") (pin "12") (pinfunction "12_12") (pintype "unspecified"))
    )
    (net (code "31") (name "/c12") (class "Default")
      (node (ref "ADDRESSCHECKER1") (pin "12") (pinfunction "Q4_12") (pintype "unspecified"))
      (node (ref "RN1") (pin "5") (pinfunction "5_5") (pintype "input"))
      (node (ref "S1") (pin "13") (pinfunction "13_13") (pintype "unspecified"))
    )
    (net (code "32") (name "/c13") (class "Default")
      (node (ref "ADDRESSCHECKER1") (pin "14") (pinfunction "Q5_14") (pintype "unspecified"))
      (node (ref "RN1") (pin "4") (pinfunction "4_4") (pintype "input"))
      (node (ref "S1") (pin "14") (pinfunction "14_14") (pintype "unspecified"))
    )
    (net (code "33") (name "/c14") (class "Default")
      (node (ref "ADDRESSCHECKER1") (pin "16") (pinfunction "Q6_16") (pintype "unspecified"))
      (node (ref "RN1") (pin "3") (pinfunction "3_3") (pintype "input"))
      (node (ref "S1") (pin "15") (pinfunction "15_15") (pintype "unspecified"))
    )
    (net (code "34") (name "/c15") (class "Default")
      (node (ref "ADDRESSCHECKER1") (pin "18") (pinfunction "Q7_18") (pintype "unspecified"))
      (node (ref "RN1") (pin "2") (pinfunction "2_2") (pintype "input"))
      (node (ref "S1") (pin "16") (pinfunction "16_16") (pintype "unspecified"))
    )
    (net (code "35") (name "/clockout") (class "Default")
      (node (ref "DATAPINS1") (pin "5") (pinfunction "5_5") (pintype "unspecified"))
      (node (ref "U1") (pin "12") (pinfunction "4A_12") (pintype "unspecified"))
    )
    (net (code "36") (name "/d0") (class "Default")
      (node (ref "DATAPINS1") (pin "9") (pinfunction "9_9") (pintype "unspecified"))
      (node (ref "REG1") (pin "9") (pinfunction "Q3_9") (pintype "unspecified"))
      (node (ref "REG2") (pin "9") (pinfunction "Q3_9") (pintype "unspecified"))
      (node (ref "REG3") (pin "9") (pinfunction "Q3_9") (pintype "unspecified"))
      (node (ref "REG4") (pin "9") (pinfunction "Q3_9") (pintype "unspecified"))
      (node (ref "REG5") (pin "9") (pinfunction "Q3_9") (pintype "unspecified"))
      (node (ref "REG6") (pin "9") (pinfunction "Q3_9") (pintype "unspecified"))
      (node (ref "REG7") (pin "9") (pinfunction "Q3_9") (pintype "unspecified"))
      (node (ref "REG8") (pin "9") (pinfunction "Q3_9") (pintype "unspecified"))
    )
    (net (code "37") (name "/d1") (class "Default")
      (node (ref "DATAPINS1") (pin "10") (pinfunction "10_10") (pintype "unspecified"))
      (node (ref "REG1") (pin "8") (pinfunction "D3_8") (pintype "unspecified"))
      (node (ref "REG2") (pin "8") (pinfunction "D3_8") (pintype "unspecified"))
      (node (ref "REG3") (pin "8") (pinfunction "D3_8") (pintype "unspecified"))
      (node (ref "REG4") (pin "8") (pinfunction "D3_8") (pintype "unspecified"))
      (node (ref "REG5") (pin "8") (pinfunction "D3_8") (pintype "unspecified"))
      (node (ref "REG6") (pin "8") (pinfunction "D3_8") (pintype "unspecified"))
      (node (ref "REG7") (pin "8") (pinfunction "D3_8") (pintype "unspecified"))
      (node (ref "REG8") (pin "8") (pinfunction "D3_8") (pintype "unspecified"))
    )
    (net (code "38") (name "/d2") (class "Default")
      (node (ref "DATAPINS1") (pin "11") (pinfunction "11_11") (pintype "unspecified"))
      (node (ref "REG1") (pin "7") (pinfunction "D2_7") (pintype "unspecified"))
      (node (ref "REG2") (pin "7") (pinfunction "D2_7") (pintype "unspecified"))
      (node (ref "REG3") (pin "7") (pinfunction "D2_7") (pintype "unspecified"))
      (node (ref "REG4") (pin "7") (pinfunction "D2_7") (pintype "unspecified"))
      (node (ref "REG5") (pin "7") (pinfunction "D2_7") (pintype "unspecified"))
      (node (ref "REG6") (pin "7") (pinfunction "D2_7") (pintype "unspecified"))
      (node (ref "REG7") (pin "7") (pinfunction "D2_7") (pintype "unspecified"))
      (node (ref "REG8") (pin "7") (pinfunction "D2_7") (pintype "unspecified"))
    )
    (net (code "39") (name "/d3") (class "Default")
      (node (ref "DATAPINS1") (pin "12") (pinfunction "12_12") (pintype "unspecified"))
      (node (ref "REG1") (pin "6") (pinfunction "Q2_6") (pintype "unspecified"))
      (node (ref "REG2") (pin "6") (pinfunction "Q2_6") (pintype "unspecified"))
      (node (ref "REG3") (pin "6") (pinfunction "Q2_6") (pintype "unspecified"))
      (node (ref "REG4") (pin "6") (pinfunction "Q2_6") (pintype "unspecified"))
      (node (ref "REG5") (pin "6") (pinfunction "Q2_6") (pintype "unspecified"))
      (node (ref "REG6") (pin "6") (pinfunction "Q2_6") (pintype "unspecified"))
      (node (ref "REG7") (pin "6") (pinfunction "Q2_6") (pintype "unspecified"))
      (node (ref "REG8") (pin "6") (pinfunction "Q2_6") (pintype "unspecified"))
    )
    (net (code "40") (name "/d4") (class "Default")
      (node (ref "DATAPINS1") (pin "13") (pinfunction "13_13") (pintype "unspecified"))
      (node (ref "REG1") (pin "5") (pinfunction "Q1_5") (pintype "unspecified"))
      (node (ref "REG2") (pin "5") (pinfunction "Q1_5") (pintype "unspecified"))
      (node (ref "REG3") (pin "5") (pinfunction "Q1_5") (pintype "unspecified"))
      (node (ref "REG4") (pin "5") (pinfunction "Q1_5") (pintype "unspecified"))
      (node (ref "REG5") (pin "5") (pinfunction "Q1_5") (pintype "unspecified"))
      (node (ref "REG6") (pin "5") (pinfunction "Q1_5") (pintype "unspecified"))
      (node (ref "REG7") (pin "5") (pinfunction "Q1_5") (pintype "unspecified"))
      (node (ref "REG8") (pin "5") (pinfunction "Q1_5") (pintype "unspecified"))
    )
    (net (code "41") (name "/d5") (class "Default")
      (node (ref "DATAPINS1") (pin "14") (pinfunction "14_14") (pintype "unspecified"))
      (node (ref "REG1") (pin "4") (pinfunction "D1_4") (pintype "unspecified"))
      (node (ref "REG2") (pin "4") (pinfunction "D1_4") (pintype "unspecified"))
      (node (ref "REG3") (pin "4") (pinfunction "D1_4") (pintype "unspecified"))
      (node (ref "REG4") (pin "4") (pinfunction "D1_4") (pintype "unspecified"))
      (node (ref "REG5") (pin "4") (pinfunction "D1_4") (pintype "unspecified"))
      (node (ref "REG6") (pin "4") (pinfunction "D1_4") (pintype "unspecified"))
      (node (ref "REG7") (pin "4") (pinfunction "D1_4") (pintype "unspecified"))
      (node (ref "REG8") (pin "4") (pinfunction "D1_4") (pintype "unspecified"))
    )
    (net (code "42") (name "/d6") (class "Default")
      (node (ref "DATAPINS1") (pin "15") (pinfunction "15_15") (pintype "unspecified"))
      (node (ref "REG1") (pin "3") (pinfunction "D0_3") (pintype "unspecified"))
      (node (ref "REG2") (pin "3") (pinfunction "D0_3") (pintype "unspecified"))
      (node (ref "REG3") (pin "3") (pinfunction "D0_3") (pintype "unspecified"))
      (node (ref "REG4") (pin "3") (pinfunction "D0_3") (pintype "unspecified"))
      (node (ref "REG5") (pin "3") (pinfunction "D0_3") (pintype "unspecified"))
      (node (ref "REG6") (pin "3") (pinfunction "D0_3") (pintype "unspecified"))
      (node (ref "REG7") (pin "3") (pinfunction "D0_3") (pintype "unspecified"))
      (node (ref "REG8") (pin "3") (pinfunction "D0_3") (pintype "unspecified"))
    )
    (net (code "43") (name "/d7") (class "Default")
      (node (ref "DATAPINS1") (pin "16") (pinfunction "16_16") (pintype "unspecified"))
      (node (ref "REG1") (pin "2") (pinfunction "Q0_2") (pintype "unspecified"))
      (node (ref "REG2") (pin "2") (pinfunction "Q0_2") (pintype "unspecified"))
      (node (ref "REG3") (pin "2") (pinfunction "Q0_2") (pintype "unspecified"))
      (node (ref "REG4") (pin "2") (pinfunction "Q0_2") (pintype "unspecified"))
      (node (ref "REG5") (pin "2") (pinfunction "Q0_2") (pintype "unspecified"))
      (node (ref "REG6") (pin "2") (pinfunction "Q0_2") (pintype "unspecified"))
      (node (ref "REG7") (pin "2") (pinfunction "Q0_2") (pintype "unspecified"))
      (node (ref "REG8") (pin "2") (pinfunction "Q0_2") (pintype "unspecified"))
    )
    (net (code "44") (name "/disableram") (class "Default")
      (node (ref "DATAPINS1") (pin "8") (pinfunction "8_8") (pintype "unspecified"))
    )
    (net (code "45") (name "/input1") (class "Default")
      (node (ref "INPUT1HEADER") (pin "1") (pinfunction "1_1") (pintype "input"))
      (node (ref "INPUT1HEADER") (pin "3") (pinfunction "3_3") (pintype "input"))
    )
    (net (code "46") (name "/input2") (class "Default")
      (node (ref "INPUT2HEADER") (pin "1") (pinfunction "1_1") (pintype "input"))
      (node (ref "INPUT2HEADER") (pin "3") (pinfunction "3_3") (pintype "input"))
    )
    (net (code "47") (name "/input3") (class "Default")
      (node (ref "INPUT3HEADER") (pin "1") (pinfunction "1_1") (pintype "input"))
      (node (ref "INPUT3HEADER") (pin "3") (pinfunction "3_3") (pintype "input"))
    )
    (net (code "48") (name "/input4") (class "Default")
      (node (ref "INPUT4HEADER") (pin "1") (pinfunction "1_1") (pintype "input"))
      (node (ref "INPUT4HEADER") (pin "3") (pinfunction "3_3") (pintype "input"))
    )
    (net (code "49") (name "/irq") (class "Default")
      (node (ref "DATAPINS1") (pin "4") (pinfunction "4_4") (pintype "unspecified"))
    )
    (net (code "50") (name "/nmi") (class "Default")
      (node (ref "DATAPINS1") (pin "3") (pinfunction "3_3") (pintype "unspecified"))
    )
    (net (code "51") (name "/peq1") (class "Default")
      (node (ref "ADDRESSCHECKER1") (pin "19") (pinfunction "#P=Q_19") (pintype "unspecified"))
      (node (ref "RS1") (pin "4") (pinfunction "G0#_4") (pintype "unspecified"))
    )
    (net (code "52") (name "/peq2") (class "Default")
      (node (ref "ADDRESSCHECKER2") (pin "19") (pinfunction "#P=Q_19") (pintype "unspecified"))
      (node (ref "RS1") (pin "5") (pinfunction "G1#_5") (pintype "unspecified"))
    )
    (net (code "53") (name "/r1D0") (class "Default")
      (node (ref "LED8") (pin "1") (pinfunction "1_1") (pintype "unspecified"))
      (node (ref "OUTPUTF1") (pin "8") (pinfunction "8_8") (pintype "unspecified"))
      (node (ref "REG1") (pin "12") (pinfunction "Q4_12") (pintype "unspecified"))
    )
    (net (code "54") (name "/r1D1") (class "Default")
      (node (ref "LED7") (pin "1") (pinfunction "1_1") (pintype "unspecified"))
      (node (ref "OUTPUTF1") (pin "7") (pinfunction "7_7") (pintype "unspecified"))
      (node (ref "REG1") (pin "13") (pinfunction "D4_13") (pintype "unspecified"))
    )
    (net (code "55") (name "/r1D2") (class "Default")
      (node (ref "LED6") (pin "1") (pinfunction "1_1") (pintype "unspecified"))
      (node (ref "OUTPUTF1") (pin "6") (pinfunction "6_6") (pintype "unspecified"))
      (node (ref "REG1") (pin "14") (pinfunction "D5_14") (pintype "unspecified"))
    )
    (net (code "56") (name "/r1D3") (class "Default")
      (node (ref "LED5") (pin "1") (pinfunction "1_1") (pintype "unspecified"))
      (node (ref "OUTPUTF1") (pin "5") (pinfunction "5_5") (pintype "unspecified"))
      (node (ref "REG1") (pin "15") (pinfunction "Q5_15") (pintype "unspecified"))
    )
    (net (code "57") (name "/r1D4") (class "Default")
      (node (ref "LED4") (pin "1") (pinfunction "1_1") (pintype "unspecified"))
      (node (ref "OUTPUTF1") (pin "4") (pinfunction "4_4") (pintype "unspecified"))
      (node (ref "REG1") (pin "16") (pinfunction "Q6_16") (pintype "unspecified"))
    )
    (net (code "58") (name "/r1D5") (class "Default")
      (node (ref "LED3") (pin "1") (pinfunction "1_1") (pintype "unspecified"))
      (node (ref "OUTPUTF1") (pin "3") (pinfunction "3_3") (pintype "unspecified"))
      (node (ref "REG1") (pin "17") (pinfunction "D6_17") (pintype "unspecified"))
    )
    (net (code "59") (name "/r1D6") (class "Default")
      (node (ref "LED2") (pin "1") (pinfunction "1_1") (pintype "unspecified"))
      (node (ref "OUTPUTF1") (pin "2") (pinfunction "2_2") (pintype "unspecified"))
      (node (ref "REG1") (pin "18") (pinfunction "D7_18") (pintype "unspecified"))
    )
    (net (code "60") (name "/r1D7") (class "Default")
      (node (ref "LED1") (pin "1") (pinfunction "1_1") (pintype "unspecified"))
      (node (ref "OUTPUTF1") (pin "1") (pinfunction "1_1") (pintype "unspecified"))
      (node (ref "REG1") (pin "19") (pinfunction "Q7_19") (pintype "unspecified"))
    )
    (net (code "61") (name "/r2D0") (class "Default")
      (node (ref "REG2") (pin "12") (pinfunction "Q4_12") (pintype "unspecified"))
    )
    (net (code "62") (name "/r2D1") (class "Default")
      (node (ref "REG2") (pin "13") (pinfunction "D4_13") (pintype "unspecified"))
    )
    (net (code "63") (name "/r2D2") (class "Default")
      (node (ref "LED11") (pin "1") (pinfunction "1_1") (pintype "unspecified"))
      (node (ref "OUTPUTV1") (pin "6") (pinfunction "6_6") (pintype "unspecified"))
      (node (ref "REG2") (pin "14") (pinfunction "D5_14") (pintype "unspecified"))
    )
    (net (code "64") (name "/r2D3") (class "Default")
      (node (ref "LED12") (pin "1") (pinfunction "1_1") (pintype "unspecified"))
      (node (ref "OUTPUTV1") (pin "5") (pinfunction "5_5") (pintype "unspecified"))
      (node (ref "REG2") (pin "15") (pinfunction "Q5_15") (pintype "unspecified"))
    )
    (net (code "65") (name "/r2D4") (class "Default")
      (node (ref "LED13") (pin "1") (pinfunction "1_1") (pintype "unspecified"))
      (node (ref "OUTPUTV1") (pin "4") (pinfunction "4_4") (pintype "unspecified"))
      (node (ref "REG2") (pin "16") (pinfunction "Q6_16") (pintype "unspecified"))
    )
    (net (code "66") (name "/r2D5") (class "Default")
      (node (ref "LED14") (pin "1") (pinfunction "1_1") (pintype "unspecified"))
      (node (ref "OUTPUTV1") (pin "3") (pinfunction "3_3") (pintype "unspecified"))
      (node (ref "REG2") (pin "17") (pinfunction "D6_17") (pintype "unspecified"))
    )
    (net (code "67") (name "/r2D6") (class "Default")
      (node (ref "LED15") (pin "1") (pinfunction "1_1") (pintype "unspecified"))
      (node (ref "LED41") (pin "1") (pinfunction "1_1") (pintype "unspecified"))
      (node (ref "OUTPUTV1") (pin "2") (pinfunction "2_2") (pintype "unspecified"))
      (node (ref "OUTPUTV3") (pin "2") (pinfunction "2_2") (pintype "unspecified"))
      (node (ref "REG2") (pin "18") (pinfunction "D7_18") (pintype "unspecified"))
      (node (ref "REG6") (pin "18") (pinfunction "D7_18") (pintype "unspecified"))
    )
    (net (code "68") (name "/r2D7") (class "Default")
      (node (ref "LED16") (pin "1") (pinfunction "1_1") (pintype "unspecified"))
      (node (ref "OUTPUTV1") (pin "1") (pinfunction "1_1") (pintype "unspecified"))
      (node (ref "REG2") (pin "19") (pinfunction "Q7_19") (pintype "unspecified"))
    )
    (net (code "69") (name "/r3D0") (class "Default")
      (node (ref "LED25") (pin "1") (pinfunction "1_1") (pintype "unspecified"))
      (node (ref "OUTPUTF2") (pin "8") (pinfunction "8_8") (pintype "unspecified"))
      (node (ref "REG3") (pin "12") (pinfunction "Q4_12") (pintype "unspecified"))
    )
    (net (code "70") (name "/r3D1") (class "Default")
      (node (ref "LED26") (pin "1") (pinfunction "1_1") (pintype "unspecified"))
      (node (ref "OUTPUTF2") (pin "7") (pinfunction "7_7") (pintype "unspecified"))
      (node (ref "REG3") (pin "13") (pinfunction "D4_13") (pintype "unspecified"))
    )
    (net (code "71") (name "/r3D2") (class "Default")
      (node (ref "LED27") (pin "1") (pinfunction "1_1") (pintype "unspecified"))
      (node (ref "OUTPUTF2") (pin "6") (pinfunction "6_6") (pintype "unspecified"))
      (node (ref "REG3") (pin "14") (pinfunction "D5_14") (pintype "unspecified"))
    )
    (net (code "72") (name "/r3D3") (class "Default")
      (node (ref "LED28") (pin "1") (pinfunction "1_1") (pintype "unspecified"))
      (node (ref "OUTPUTF2") (pin "5") (pinfunction "5_5") (pintype "unspecified"))
      (node (ref "REG3") (pin "15") (pinfunction "Q5_15") (pintype "unspecified"))
    )
    (net (code "73") (name "/r3D4") (class "Default")
      (node (ref "LED29") (pin "1") (pinfunction "1_1") (pintype "unspecified"))
      (node (ref "OUTPUTF2") (pin "4") (pinfunction "4_4") (pintype "unspecified"))
      (node (ref "REG3") (pin "16") (pinfunction "Q6_16") (pintype "unspecified"))
    )
    (net (code "74") (name "/r3D5") (class "Default")
      (node (ref "LED30") (pin "1") (pinfunction "1_1") (pintype "unspecified"))
      (node (ref "OUTPUTF2") (pin "3") (pinfunction "3_3") (pintype "unspecified"))
      (node (ref "REG3") (pin "17") (pinfunction "D6_17") (pintype "unspecified"))
    )
    (net (code "75") (name "/r3D6") (class "Default")
      (node (ref "LED31") (pin "1") (pinfunction "1_1") (pintype "unspecified"))
      (node (ref "OUTPUTF2") (pin "2") (pinfunction "2_2") (pintype "unspecified"))
      (node (ref "REG3") (pin "18") (pinfunction "D7_18") (pintype "unspecified"))
    )
    (net (code "76") (name "/r3D7") (class "Default")
      (node (ref "LED32") (pin "1") (pinfunction "1_1") (pintype "unspecified"))
      (node (ref "OUTPUTF2") (pin "1") (pinfunction "1_1") (pintype "unspecified"))
      (node (ref "REG3") (pin "19") (pinfunction "Q7_19") (pintype "unspecified"))
    )
    (net (code "77") (name "/r4D0") (class "Default")
      (node (ref "REG4") (pin "12") (pinfunction "Q4_12") (pintype "unspecified"))
    )
    (net (code "78") (name "/r4D1") (class "Default")
      (node (ref "REG4") (pin "13") (pinfunction "D4_13") (pintype "unspecified"))
    )
    (net (code "79") (name "/r4D2") (class "Default")
      (node (ref "LED22") (pin "1") (pinfunction "1_1") (pintype "unspecified"))
      (node (ref "OUTPUTV2") (pin "6") (pinfunction "6_6") (pintype "unspecified"))
      (node (ref "REG4") (pin "14") (pinfunction "D5_14") (pintype "unspecified"))
    )
    (net (code "80") (name "/r4D3") (class "Default")
      (node (ref "LED21") (pin "1") (pinfunction "1_1") (pintype "unspecified"))
      (node (ref "OUTPUTV2") (pin "5") (pinfunction "5_5") (pintype "unspecified"))
      (node (ref "REG4") (pin "15") (pinfunction "Q5_15") (pintype "unspecified"))
    )
    (net (code "81") (name "/r4D4") (class "Default")
      (node (ref "LED20") (pin "1") (pinfunction "1_1") (pintype "unspecified"))
      (node (ref "OUTPUTV2") (pin "4") (pinfunction "4_4") (pintype "unspecified"))
      (node (ref "REG4") (pin "16") (pinfunction "Q6_16") (pintype "unspecified"))
    )
    (net (code "82") (name "/r4D5") (class "Default")
      (node (ref "LED19") (pin "1") (pinfunction "1_1") (pintype "unspecified"))
      (node (ref "OUTPUTV2") (pin "3") (pinfunction "3_3") (pintype "unspecified"))
      (node (ref "REG4") (pin "17") (pinfunction "D6_17") (pintype "unspecified"))
    )
    (net (code "83") (name "/r4D6") (class "Default")
      (node (ref "LED18") (pin "1") (pinfunction "1_1") (pintype "unspecified"))
      (node (ref "OUTPUTV2") (pin "2") (pinfunction "2_2") (pintype "unspecified"))
      (node (ref "REG4") (pin "18") (pinfunction "D7_18") (pintype "unspecified"))
    )
    (net (code "84") (name "/r4D7") (class "Default")
      (node (ref "LED17") (pin "1") (pinfunction "1_1") (pintype "unspecified"))
      (node (ref "OUTPUTV2") (pin "1") (pinfunction "1_1") (pintype "unspecified"))
      (node (ref "REG4") (pin "19") (pinfunction "Q7_19") (pintype "unspecified"))
    )
    (net (code "85") (name "/r5D0") (class "Default")
      (node (ref "LED36") (pin "1") (pinfunction "1_1") (pintype "unspecified"))
      (node (ref "OUTPUTF3") (pin "8") (pinfunction "8_8") (pintype "unspecified"))
      (node (ref "REG5") (pin "12") (pinfunction "Q4_12") (pintype "unspecified"))
    )
    (net (code "86") (name "/r5D1") (class "Default")
      (node (ref "LED35") (pin "1") (pinfunction "1_1") (pintype "unspecified"))
      (node (ref "OUTPUTF3") (pin "7") (pinfunction "7_7") (pintype "unspecified"))
      (node (ref "REG5") (pin "13") (pinfunction "D4_13") (pintype "unspecified"))
    )
    (net (code "87") (name "/r5D2") (class "Default")
      (node (ref "LED34") (pin "1") (pinfunction "1_1") (pintype "unspecified"))
      (node (ref "OUTPUTF3") (pin "6") (pinfunction "6_6") (pintype "unspecified"))
      (node (ref "REG5") (pin "14") (pinfunction "D5_14") (pintype "unspecified"))
    )
    (net (code "88") (name "/r5D3") (class "Default")
      (node (ref "LED33") (pin "1") (pinfunction "1_1") (pintype "unspecified"))
      (node (ref "OUTPUTF3") (pin "5") (pinfunction "5_5") (pintype "unspecified"))
      (node (ref "REG5") (pin "15") (pinfunction "Q5_15") (pintype "unspecified"))
    )
    (net (code "89") (name "/r5D4") (class "Default")
      (node (ref "LED24") (pin "1") (pinfunction "1_1") (pintype "unspecified"))
      (node (ref "OUTPUTF3") (pin "4") (pinfunction "4_4") (pintype "unspecified"))
      (node (ref "REG5") (pin "16") (pinfunction "Q6_16") (pintype "unspecified"))
    )
    (net (code "90") (name "/r5D5") (class "Default")
      (node (ref "LED23") (pin "1") (pinfunction "1_1") (pintype "unspecified"))
      (node (ref "OUTPUTF3") (pin "3") (pinfunction "3_3") (pintype "unspecified"))
      (node (ref "REG5") (pin "17") (pinfunction "D6_17") (pintype "unspecified"))
    )
    (net (code "91") (name "/r5D6") (class "Default")
      (node (ref "LED10") (pin "1") (pinfunction "1_1") (pintype "unspecified"))
      (node (ref "OUTPUTF3") (pin "2") (pinfunction "2_2") (pintype "unspecified"))
      (node (ref "REG5") (pin "18") (pinfunction "D7_18") (pintype "unspecified"))
    )
    (net (code "92") (name "/r5D7") (class "Default")
      (node (ref "LED9") (pin "1") (pinfunction "1_1") (pintype "unspecified"))
      (node (ref "OUTPUTF3") (pin "1") (pinfunction "1_1") (pintype "unspecified"))
      (node (ref "REG5") (pin "19") (pinfunction "Q7_19") (pintype "unspecified"))
    )
    (net (code "93") (name "/r6D0") (class "Default")
      (node (ref "REG6") (pin "12") (pinfunction "Q4_12") (pintype "unspecified"))
    )
    (net (code "94") (name "/r6D1") (class "Default")
      (node (ref "REG6") (pin "13") (pinfunction "D4_13") (pintype "unspecified"))
    )
    (net (code "95") (name "/r6D2") (class "Default")
      (node (ref "LED37") (pin "1") (pinfunction "1_1") (pintype "unspecified"))
      (node (ref "OUTPUTV3") (pin "6") (pinfunction "6_6") (pintype "unspecified"))
      (node (ref "REG6") (pin "14") (pinfunction "D5_14") (pintype "unspecified"))
    )
    (net (code "96") (name "/r6D3") (class "Default")
      (node (ref "LED38") (pin "1") (pinfunction "1_1") (pintype "unspecified"))
      (node (ref "OUTPUTV3") (pin "5") (pinfunction "5_5") (pintype "unspecified"))
      (node (ref "REG6") (pin "15") (pinfunction "Q5_15") (pintype "unspecified"))
    )
    (net (code "97") (name "/r6D4") (class "Default")
      (node (ref "LED39") (pin "1") (pinfunction "1_1") (pintype "unspecified"))
      (node (ref "OUTPUTV3") (pin "4") (pinfunction "4_4") (pintype "unspecified"))
      (node (ref "REG6") (pin "16") (pinfunction "Q6_16") (pintype "unspecified"))
    )
    (net (code "98") (name "/r6D5") (class "Default")
      (node (ref "LED40") (pin "1") (pinfunction "1_1") (pintype "unspecified"))
      (node (ref "OUTPUTV3") (pin "3") (pinfunction "3_3") (pintype "unspecified"))
      (node (ref "REG6") (pin "17") (pinfunction "D6_17") (pintype "unspecified"))
    )
    (net (code "99") (name "/r6D7") (class "Default")
      (node (ref "LED42") (pin "1") (pinfunction "1_1") (pintype "unspecified"))
      (node (ref "OUTPUTV3") (pin "1") (pinfunction "1_1") (pintype "unspecified"))
      (node (ref "REG6") (pin "19") (pinfunction "Q7_19") (pintype "unspecified"))
    )
    (net (code "100") (name "/r7D0") (class "Default")
      (node (ref "LED49") (pin "1") (pinfunction "1_1") (pintype "unspecified"))
      (node (ref "OUTPUTF4") (pin "8") (pinfunction "8_8") (pintype "unspecified"))
      (node (ref "REG8") (pin "12") (pinfunction "Q4_12") (pintype "unspecified"))
    )
    (net (code "101") (name "/r7D1") (class "Default")
      (node (ref "LED50") (pin "1") (pinfunction "1_1") (pintype "unspecified"))
      (node (ref "OUTPUTF4") (pin "7") (pinfunction "7_7") (pintype "unspecified"))
      (node (ref "REG8") (pin "13") (pinfunction "D4_13") (pintype "unspecified"))
    )
    (net (code "102") (name "/r7D2") (class "Default")
      (node (ref "LED51") (pin "1") (pinfunction "1_1") (pintype "unspecified"))
      (node (ref "OUTPUTF4") (pin "6") (pinfunction "6_6") (pintype "unspecified"))
      (node (ref "REG8") (pin "14") (pinfunction "D5_14") (pintype "unspecified"))
    )
    (net (code "103") (name "/r7D3") (class "Default")
      (node (ref "LED52") (pin "1") (pinfunction "1_1") (pintype "unspecified"))
      (node (ref "OUTPUTF4") (pin "5") (pinfunction "5_5") (pintype "unspecified"))
      (node (ref "REG8") (pin "15") (pinfunction "Q5_15") (pintype "unspecified"))
    )
    (net (code "104") (name "/r7D4") (class "Default")
      (node (ref "LED53") (pin "1") (pinfunction "1_1") (pintype "unspecified"))
      (node (ref "OUTPUTF4") (pin "4") (pinfunction "4_4") (pintype "unspecified"))
      (node (ref "REG8") (pin "16") (pinfunction "Q6_16") (pintype "unspecified"))
    )
    (net (code "105") (name "/r7D5") (class "Default")
      (node (ref "LED54") (pin "1") (pinfunction "1_1") (pintype "unspecified"))
      (node (ref "OUTPUTF4") (pin "3") (pinfunction "3_3") (pintype "unspecified"))
      (node (ref "REG8") (pin "17") (pinfunction "D6_17") (pintype "unspecified"))
    )
    (net (code "106") (name "/r7D6") (class "Default")
      (node (ref "LED55") (pin "1") (pinfunction "1_1") (pintype "unspecified"))
      (node (ref "OUTPUTF4") (pin "2") (pinfunction "2_2") (pintype "unspecified"))
      (node (ref "REG8") (pin "18") (pinfunction "D7_18") (pintype "unspecified"))
    )
    (net (code "107") (name "/r7D7") (class "Default")
      (node (ref "LED56") (pin "1") (pinfunction "1_1") (pintype "unspecified"))
      (node (ref "OUTPUTF4") (pin "1") (pinfunction "1_1") (pintype "unspecified"))
      (node (ref "REG8") (pin "19") (pinfunction "Q7_19") (pintype "unspecified"))
    )
    (net (code "108") (name "/r8D0") (class "Default")
      (node (ref "REG7") (pin "12") (pinfunction "Q4_12") (pintype "unspecified"))
    )
    (net (code "109") (name "/r8D1") (class "Default")
      (node (ref "REG7") (pin "13") (pinfunction "D4_13") (pintype "unspecified"))
    )
    (net (code "110") (name "/r8D2") (class "Default")
      (node (ref "LED48") (pin "1") (pinfunction "1_1") (pintype "unspecified"))
      (node (ref "OUTPUTV4") (pin "6") (pinfunction "6_6") (pintype "unspecified"))
      (node (ref "REG7") (pin "14") (pinfunction "D5_14") (pintype "unspecified"))
    )
    (net (code "111") (name "/r8D3") (class "Default")
      (node (ref "LED47") (pin "1") (pinfunction "1_1") (pintype "unspecified"))
      (node (ref "OUTPUTV4") (pin "5") (pinfunction "5_5") (pintype "unspecified"))
      (node (ref "REG7") (pin "15") (pinfunction "Q5_15") (pintype "unspecified"))
    )
    (net (code "112") (name "/r8D4") (class "Default")
      (node (ref "LED46") (pin "1") (pinfunction "1_1") (pintype "unspecified"))
      (node (ref "OUTPUTV4") (pin "4") (pinfunction "4_4") (pintype "unspecified"))
      (node (ref "REG7") (pin "16") (pinfunction "Q6_16") (pintype "unspecified"))
    )
    (net (code "113") (name "/r8D5") (class "Default")
      (node (ref "LED45") (pin "1") (pinfunction "1_1") (pintype "unspecified"))
      (node (ref "OUTPUTV4") (pin "3") (pinfunction "3_3") (pintype "unspecified"))
      (node (ref "REG7") (pin "17") (pinfunction "D6_17") (pintype "unspecified"))
    )
    (net (code "114") (name "/r8D6") (class "Default")
      (node (ref "LED44") (pin "1") (pinfunction "1_1") (pintype "unspecified"))
      (node (ref "OUTPUTV4") (pin "2") (pinfunction "2_2") (pintype "unspecified"))
      (node (ref "REG7") (pin "18") (pinfunction "D7_18") (pintype "unspecified"))
    )
    (net (code "115") (name "/r8D7") (class "Default")
      (node (ref "LED43") (pin "1") (pinfunction "1_1") (pintype "unspecified"))
      (node (ref "OUTPUTV4") (pin "1") (pinfunction "1_1") (pintype "unspecified"))
      (node (ref "REG7") (pin "19") (pinfunction "Q7_19") (pintype "unspecified"))
    )
    (net (code "116") (name "/rsE") (class "Default")
      (node (ref "RS1") (pin "6") (pinfunction "G2_6") (pintype "unspecified"))
      (node (ref "U1") (pin "11") (pinfunction "4Y_11") (pintype "unspecified"))
    )
    (net (code "117") (name "/r{slash}w") (class "Default")
      (node (ref "DATAPINS1") (pin "7") (pinfunction "7_7") (pintype "unspecified"))
      (node (ref "NOR1") (pin "8") (pinfunction "A3_8") (pintype "unspecified"))
      (node (ref "NOR1") (pin "9") (pinfunction "B3_9") (pintype "unspecified"))
    )
    (net (code "118") (name "/r{slash}wNot") (class "Default")
      (node (ref "NOR1") (pin "10") (pinfunction "Y3_10") (pintype "unspecified"))
      (node (ref "U1") (pin "13") (pinfunction "4B_13") (pintype "unspecified"))
    )
    (net (code "119") (name "/soundOutput1") (class "Default")
      (node (ref "REG2") (pin "1") (pinfunction "E#_1") (pintype "unspecified"))
      (node (ref "REG6") (pin "1") (pinfunction "E#_1") (pintype "unspecified"))
    )
    (net (code "120") (name "/soundOutput2") (class "Default")
      (node (ref "REG4") (pin "1") (pinfunction "E#_1") (pintype "unspecified"))
      (node (ref "REG7") (pin "1") (pinfunction "E#_1") (pintype "unspecified"))
    )
    (net (code "121") (name "/store1") (class "Default")
      (node (ref "REG1") (pin "11") (pinfunction "CP_11") (pintype "unspecified"))
      (node (ref "RS1") (pin "15") (pinfunction "Y0_15") (pintype "unspecified"))
    )
    (net (code "122") (name "/store2") (class "Default")
      (node (ref "REG2") (pin "11") (pinfunction "CP_11") (pintype "unspecified"))
      (node (ref "RS1") (pin "14") (pinfunction "Y1_14") (pintype "unspecified"))
    )
    (net (code "123") (name "/store3") (class "Default")
      (node (ref "REG3") (pin "11") (pinfunction "CP_11") (pintype "unspecified"))
      (node (ref "RS1") (pin "13") (pinfunction "Y2_13") (pintype "unspecified"))
    )
    (net (code "124") (name "/store4") (class "Default")
      (node (ref "REG4") (pin "11") (pinfunction "CP_11") (pintype "unspecified"))
      (node (ref "RS1") (pin "12") (pinfunction "Y3_12") (pintype "unspecified"))
    )
    (net (code "125") (name "/store5") (class "Default")
      (node (ref "REG5") (pin "11") (pinfunction "CP_11") (pintype "unspecified"))
      (node (ref "RS1") (pin "11") (pinfunction "Y4_11") (pintype "unspecified"))
    )
    (net (code "126") (name "/store6") (class "Default")
      (node (ref "REG6") (pin "11") (pinfunction "CP_11") (pintype "unspecified"))
      (node (ref "RS1") (pin "10") (pinfunction "Y5_10") (pintype "unspecified"))
    )
    (net (code "127") (name "/store7") (class "Default")
      (node (ref "REG8") (pin "11") (pinfunction "CP_11") (pintype "unspecified"))
      (node (ref "RS1") (pin "9") (pinfunction "Y6_9") (pintype "unspecified"))
    )
    (net (code "128") (name "/store8") (class "Default")
      (node (ref "REG7") (pin "11") (pinfunction "CP_11") (pintype "unspecified"))
      (node (ref "RS1") (pin "7") (pinfunction "Y7_7") (pintype "unspecified"))
    )
    (net (code "129") (name "/totalSoundOutput") (class "Default")
      (node (ref "BUZZER1") (pin "2") (pinfunction "+_2") (pintype "unspecified"))
      (node (ref "COMBINEDOUTPUT1") (pin "1") (pinfunction "1_1") (pintype "input"))
    )
    (net (code "130") (name "GND") (class "Default")
      (node (ref "ADDRESSCHECKER1") (pin "10") (pinfunction "GND_10") (pintype "unspecified"))
      (node (ref "ADDRESSCHECKER2") (pin "10") (pinfunction "GND_10") (pintype "unspecified"))
      (node (ref "ADDRESSCHECKER2") (pin "2") (pinfunction "P0_2") (pintype "unspecified"))
      (node (ref "ADDRESSCHECKER2") (pin "3") (pinfunction "Q0_3") (pintype "unspecified"))
      (node (ref "ADDRESSCHECKER2") (pin "4") (pinfunction "P1_4") (pintype "unspecified"))
      (node (ref "ADDRESSCHECKER2") (pin "5") (pinfunction "Q1_5") (pintype "unspecified"))
      (node (ref "ADDRESSCHECKER2") (pin "6") (pinfunction "P2_6") (pintype "unspecified"))
      (node (ref "ADDRESSCHECKER2") (pin "7") (pinfunction "Q2_7") (pintype "unspecified"))
      (node (ref "COMBINEDOUTPUT1") (pin "2") (pinfunction "2_2") (pintype "input"))
      (node (ref "DATAPINS1") (pin "1") (pinfunction "1_1") (pintype "unspecified"))
      (node (ref "INPUT1HEADER") (pin "2") (pinfunction "2_2") (pintype "input"))
      (node (ref "INPUT2HEADER") (pin "2") (pinfunction "2_2") (pintype "input"))
      (node (ref "INPUT3HEADER") (pin "2") (pinfunction "2_2") (pintype "input"))
      (node (ref "INPUT4HEADER") (pin "2") (pinfunction "2_2") (pintype "input"))
      (node (ref "NOR1") (pin "7") (pinfunction "GND_7") (pintype "unspecified"))
      (node (ref "R1") (pin "1") (pinfunction "1_1") (pintype "unspecified"))
      (node (ref "R11") (pin "2") (pinfunction "2_2") (pintype "unspecified"))
      (node (ref "R12") (pin "2") (pinfunction "2_2") (pintype "unspecified"))
      (node (ref "R2") (pin "1") (pinfunction "1_1") (pintype "unspecified"))
      (node (ref "R22") (pin "2") (pinfunction "2_2") (pintype "unspecified"))
      (node (ref "R29") (pin "2") (pinfunction "2_2") (pintype "unspecified"))
      (node (ref "R3") (pin "1") (pinfunction "1_1") (pintype "unspecified"))
      (node (ref "R30") (pin "2") (pinfunction "2_2") (pintype "unspecified"))
      (node (ref "R31") (pin "2") (pinfunction "2_2") (pintype "unspecified"))
      (node (ref "R32") (pin "2") (pinfunction "2_2") (pintype "unspecified"))
      (node (ref "R33") (pin "2") (pinfunction "2_2") (pintype "unspecified"))
      (node (ref "R34") (pin "2") (pinfunction "2_2") (pintype "unspecified"))
      (node (ref "R35") (pin "2") (pinfunction "2_2") (pintype "unspecified"))
      (node (ref "R36") (pin "2") (pinfunction "2_2") (pintype "unspecified"))
      (node (ref "R37") (pin "2") (pinfunction "2_2") (pintype "unspecified"))
      (node (ref "R38") (pin "2") (pinfunction "2_2") (pintype "unspecified"))
      (node (ref "R39") (pin "2") (pinfunction "2_2") (pintype "unspecified"))
      (node (ref "R4") (pin "2") (pinfunction "2_2") (pintype "unspecified"))
      (node (ref "R40") (pin "2") (pinfunction "2_2") (pintype "unspecified"))
      (node (ref "R41") (pin "2") (pinfunction "2_2") (pintype "unspecified"))
      (node (ref "R42") (pin "2") (pinfunction "2_2") (pintype "unspecified"))
      (node (ref "R43") (pin "2") (pinfunction "2_2") (pintype "unspecified"))
      (node (ref "R44") (pin "2") (pinfunction "2_2") (pintype "unspecified"))
      (node (ref "R45") (pin "2") (pinfunction "2_2") (pintype "unspecified"))
      (node (ref "R46") (pin "2") (pinfunction "2_2") (pintype "unspecified"))
      (node (ref "R47") (pin "2") (pinfunction "2_2") (pintype "unspecified"))
      (node (ref "R48") (pin "2") (pinfunction "2_2") (pintype "unspecified"))
      (node (ref "R49") (pin "2") (pinfunction "2_2") (pintype "unspecified"))
      (node (ref "R5") (pin "2") (pinfunction "2_2") (pintype "unspecified"))
      (node (ref "R50") (pin "2") (pinfunction "2_2") (pintype "unspecified"))
      (node (ref "R51") (pin "2") (pinfunction "2_2") (pintype "unspecified"))
      (node (ref "R52") (pin "2") (pinfunction "2_2") (pintype "unspecified"))
      (node (ref "R53") (pin "2") (pinfunction "2_2") (pintype "unspecified"))
      (node (ref "R54") (pin "2") (pinfunction "2_2") (pintype "unspecified"))
      (node (ref "R55") (pin "2") (pinfunction "2_2") (pintype "unspecified"))
      (node (ref "R56") (pin "2") (pinfunction "2_2") (pintype "unspecified"))
      (node (ref "R57") (pin "2") (pinfunction "2_2") (pintype "unspecified"))
      (node (ref "R58") (pin "2") (pinfunction "2_2") (pintype "unspecified"))
      (node (ref "R59") (pin "2") (pinfunction "2_2") (pintype "unspecified"))
      (node (ref "R6") (pin "2") (pinfunction "2_2") (pintype "unspecified"))
      (node (ref "R60") (pin "2") (pinfunction "2_2") (pintype "unspecified"))
      (node (ref "R61") (pin "1") (pinfunction "1_1") (pintype "unspecified"))
      (node (ref "R62") (pin "2") (pinfunction "2_2") (pintype "unspecified"))
      (node (ref "R63") (pin "2") (pinfunction "2_2") (pintype "unspecified"))
      (node (ref "R64") (pin "2") (pinfunction "2_2") (pintype "unspecified"))
      (node (ref "R65") (pin "2") (pinfunction "2_2") (pintype "unspecified"))
      (node (ref "R66") (pin "2") (pinfunction "2_2") (pintype "unspecified"))
      (node (ref "R67") (pin "2") (pinfunction "2_2") (pintype "unspecified"))
      (node (ref "R68") (pin "2") (pinfunction "2_2") (pintype "unspecified"))
      (node (ref "R69") (pin "2") (pinfunction "2_2") (pintype "unspecified"))
      (node (ref "R7") (pin "2") (pinfunction "2_2") (pintype "unspecified"))
      (node (ref "R70") (pin "2") (pinfunction "2_2") (pintype "unspecified"))
      (node (ref "R71") (pin "2") (pinfunction "2_2") (pintype "unspecified"))
      (node (ref "R72") (pin "2") (pinfunction "2_2") (pintype "unspecified"))
      (node (ref "R73") (pin "2") (pinfunction "2_2") (pintype "unspecified"))
      (node (ref "R74") (pin "2") (pinfunction "2_2") (pintype "unspecified"))
      (node (ref "R75") (pin "2") (pinfunction "2_2") (pintype "unspecified"))
      (node (ref "R76") (pin "2") (pinfunction "2_2") (pintype "unspecified"))
      (node (ref "R77") (pin "1") (pinfunction "1_1") (pintype "unspecified"))
      (node (ref "R78") (pin "1") (pinfunction "1_1") (pintype "unspecified"))
      (node (ref "R79") (pin "2") (pinfunction "2_2") (pintype "unspecified"))
      (node (ref "R8") (pin "2") (pinfunction "2_2") (pintype "unspecified"))
      (node (ref "R9") (pin "2") (pinfunction "2_2") (pintype "unspecified"))
      (node (ref "REG1") (pin "10") (pinfunction "GND_10") (pintype "unspecified"))
      (node (ref "REG2") (pin "10") (pinfunction "GND_10") (pintype "unspecified"))
      (node (ref "REG3") (pin "10") (pinfunction "GND_10") (pintype "unspecified"))
      (node (ref "REG4") (pin "10") (pinfunction "GND_10") (pintype "unspecified"))
      (node (ref "REG5") (pin "10") (pinfunction "GND_10") (pintype "unspecified"))
      (node (ref "REG6") (pin "10") (pinfunction "GND_10") (pintype "unspecified"))
      (node (ref "REG7") (pin "10") (pinfunction "GND_10") (pintype "unspecified"))
      (node (ref "REG8") (pin "10") (pinfunction "GND_10") (pintype "unspecified"))
      (node (ref "RN1") (pin "1") (pinfunction "1_1") (pintype "input"))
      (node (ref "RN2") (pin "1") (pinfunction "1_1") (pintype "input"))
      (node (ref "RS1") (pin "8") (pinfunction "GND_8") (pintype "unspecified"))
      (node (ref "U1") (pin "7") (pinfunction "GND_7") (pintype "unspecified"))
    )
    (net (code "131") (name "Net-(ADDRESSCHECKER1-OE#)") (class "Default")
      (node (ref "ADDRESSCHECKER1") (pin "1") (pinfunction "OE#_1") (pintype "unspecified"))
      (node (ref "R1") (pin "2") (pinfunction "2_2") (pintype "unspecified"))
    )
    (net (code "132") (name "Net-(ADDRESSCHECKER2-OE#)") (class "Default")
      (node (ref "ADDRESSCHECKER2") (pin "1") (pinfunction "OE#_1") (pintype "unspecified"))
      (node (ref "R2") (pin "2") (pinfunction "2_2") (pintype "unspecified"))
    )
    (net (code "133") (name "Net-(BUZZER1--)") (class "Default")
      (node (ref "BUZZER1") (pin "1") (pinfunction "-_1") (pintype "unspecified"))
      (node (ref "R79") (pin "3") (pinfunction "3_3") (pintype "unspecified"))
    )
    (net (code "134") (name "Net-(LED1-Pad2)") (class "Default")
      (node (ref "LED1") (pin "2") (pinfunction "2_2") (pintype "unspecified"))
      (node (ref "R11") (pin "1") (pinfunction "1_1") (pintype "unspecified"))
    )
    (net (code "135") (name "Net-(LED2-Pad2)") (class "Default")
      (node (ref "LED2") (pin "2") (pinfunction "2_2") (pintype "unspecified"))
      (node (ref "R22") (pin "1") (pinfunction "1_1") (pintype "unspecified"))
    )
    (net (code "136") (name "Net-(LED3-Pad2)") (class "Default")
      (node (ref "LED3") (pin "2") (pinfunction "2_2") (pintype "unspecified"))
      (node (ref "R29") (pin "1") (pinfunction "1_1") (pintype "unspecified"))
    )
    (net (code "137") (name "Net-(LED4-Pad2)") (class "Default")
      (node (ref "LED4") (pin "2") (pinfunction "2_2") (pintype "unspecified"))
      (node (ref "R30") (pin "1") (pinfunction "1_1") (pintype "unspecified"))
    )
    (net (code "138") (name "Net-(LED5-Pad2)") (class "Default")
      (node (ref "LED5") (pin "2") (pinfunction "2_2") (pintype "unspecified"))
      (node (ref "R31") (pin "1") (pinfunction "1_1") (pintype "unspecified"))
    )
    (net (code "139") (name "Net-(LED6-Pad2)") (class "Default")
      (node (ref "LED6") (pin "2") (pinfunction "2_2") (pintype "unspecified"))
      (node (ref "R32") (pin "1") (pinfunction "1_1") (pintype "unspecified"))
    )
    (net (code "140") (name "Net-(LED7-Pad2)") (class "Default")
      (node (ref "LED7") (pin "2") (pinfunction "2_2") (pintype "unspecified"))
      (node (ref "R33") (pin "1") (pinfunction "1_1") (pintype "unspecified"))
    )
    (net (code "141") (name "Net-(LED8-Pad2)") (class "Default")
      (node (ref "LED8") (pin "2") (pinfunction "2_2") (pintype "unspecified"))
      (node (ref "R34") (pin "1") (pinfunction "1_1") (pintype "unspecified"))
    )
    (net (code "142") (name "Net-(LED9-Pad2)") (class "Default")
      (node (ref "LED9") (pin "2") (pinfunction "2_2") (pintype "unspecified"))
      (node (ref "R4") (pin "1") (pinfunction "1_1") (pintype "unspecified"))
    )
    (net (code "143") (name "Net-(LED10-Pad2)") (class "Default")
      (node (ref "LED10") (pin "2") (pinfunction "2_2") (pintype "unspecified"))
      (node (ref "R5") (pin "1") (pinfunction "1_1") (pintype "unspecified"))
    )
    (net (code "144") (name "Net-(LED11-Pad2)") (class "Default")
      (node (ref "LED11") (pin "2") (pinfunction "2_2") (pintype "unspecified"))
      (node (ref "R37") (pin "1") (pinfunction "1_1") (pintype "unspecified"))
    )
    (net (code "145") (name "Net-(LED12-Pad2)") (class "Default")
      (node (ref "LED12") (pin "2") (pinfunction "2_2") (pintype "unspecified"))
      (node (ref "R38") (pin "1") (pinfunction "1_1") (pintype "unspecified"))
    )
    (net (code "146") (name "Net-(LED13-Pad2)") (class "Default")
      (node (ref "LED13") (pin "2") (pinfunction "2_2") (pintype "unspecified"))
      (node (ref "R39") (pin "1") (pinfunction "1_1") (pintype "unspecified"))
    )
    (net (code "147") (name "Net-(LED14-Pad2)") (class "Default")
      (node (ref "LED14") (pin "2") (pinfunction "2_2") (pintype "unspecified"))
      (node (ref "R40") (pin "1") (pinfunction "1_1") (pintype "unspecified"))
    )
    (net (code "148") (name "Net-(LED15-Pad2)") (class "Default")
      (node (ref "LED15") (pin "2") (pinfunction "2_2") (pintype "unspecified"))
      (node (ref "R41") (pin "1") (pinfunction "1_1") (pintype "unspecified"))
    )
    (net (code "149") (name "Net-(LED16-Pad2)") (class "Default")
      (node (ref "LED16") (pin "2") (pinfunction "2_2") (pintype "unspecified"))
      (node (ref "R42") (pin "1") (pinfunction "1_1") (pintype "unspecified"))
    )
    (net (code "150") (name "Net-(LED17-Pad2)") (class "Default")
      (node (ref "LED17") (pin "2") (pinfunction "2_2") (pintype "unspecified"))
      (node (ref "R45") (pin "1") (pinfunction "1_1") (pintype "unspecified"))
    )
    (net (code "151") (name "Net-(LED18-Pad2)") (class "Default")
      (node (ref "LED18") (pin "2") (pinfunction "2_2") (pintype "unspecified"))
      (node (ref "R46") (pin "1") (pinfunction "1_1") (pintype "unspecified"))
    )
    (net (code "152") (name "Net-(LED19-Pad2)") (class "Default")
      (node (ref "LED19") (pin "2") (pinfunction "2_2") (pintype "unspecified"))
      (node (ref "R47") (pin "1") (pinfunction "1_1") (pintype "unspecified"))
    )
    (net (code "153") (name "Net-(LED20-Pad2)") (class "Default")
      (node (ref "LED20") (pin "2") (pinfunction "2_2") (pintype "unspecified"))
      (node (ref "R48") (pin "1") (pinfunction "1_1") (pintype "unspecified"))
    )
    (net (code "154") (name "Net-(LED21-Pad2)") (class "Default")
      (node (ref "LED21") (pin "2") (pinfunction "2_2") (pintype "unspecified"))
      (node (ref "R49") (pin "1") (pinfunction "1_1") (pintype "unspecified"))
    )
    (net (code "155") (name "Net-(LED22-Pad2)") (class "Default")
      (node (ref "LED22") (pin "2") (pinfunction "2_2") (pintype "unspecified"))
      (node (ref "R50") (pin "1") (pinfunction "1_1") (pintype "unspecified"))
    )
    (net (code "156") (name "Net-(LED23-Pad2)") (class "Default")
      (node (ref "LED23") (pin "2") (pinfunction "2_2") (pintype "unspecified"))
      (node (ref "R6") (pin "1") (pinfunction "1_1") (pintype "unspecified"))
    )
    (net (code "157") (name "Net-(LED24-Pad2)") (class "Default")
      (node (ref "LED24") (pin "2") (pinfunction "2_2") (pintype "unspecified"))
      (node (ref "R7") (pin "1") (pinfunction "1_1") (pintype "unspecified"))
    )
    (net (code "158") (name "Net-(LED25-Pad2)") (class "Default")
      (node (ref "LED25") (pin "2") (pinfunction "2_2") (pintype "unspecified"))
      (node (ref "R53") (pin "1") (pinfunction "1_1") (pintype "unspecified"))
    )
    (net (code "159") (name "Net-(LED26-Pad2)") (class "Default")
      (node (ref "LED26") (pin "2") (pinfunction "2_2") (pintype "unspecified"))
      (node (ref "R54") (pin "1") (pinfunction "1_1") (pintype "unspecified"))
    )
    (net (code "160") (name "Net-(LED27-Pad2)") (class "Default")
      (node (ref "LED27") (pin "2") (pinfunction "2_2") (pintype "unspecified"))
      (node (ref "R55") (pin "1") (pinfunction "1_1") (pintype "unspecified"))
    )
    (net (code "161") (name "Net-(LED28-Pad2)") (class "Default")
      (node (ref "LED28") (pin "2") (pinfunction "2_2") (pintype "unspecified"))
      (node (ref "R56") (pin "1") (pinfunction "1_1") (pintype "unspecified"))
    )
    (net (code "162") (name "Net-(LED29-Pad2)") (class "Default")
      (node (ref "LED29") (pin "2") (pinfunction "2_2") (pintype "unspecified"))
      (node (ref "R57") (pin "1") (pinfunction "1_1") (pintype "unspecified"))
    )
    (net (code "163") (name "Net-(LED30-Pad2)") (class "Default")
      (node (ref "LED30") (pin "2") (pinfunction "2_2") (pintype "unspecified"))
      (node (ref "R58") (pin "1") (pinfunction "1_1") (pintype "unspecified"))
    )
    (net (code "164") (name "Net-(LED31-Pad2)") (class "Default")
      (node (ref "LED31") (pin "2") (pinfunction "2_2") (pintype "unspecified"))
      (node (ref "R59") (pin "1") (pinfunction "1_1") (pintype "unspecified"))
    )
    (net (code "165") (name "Net-(LED32-Pad2)") (class "Default")
      (node (ref "LED32") (pin "2") (pinfunction "2_2") (pintype "unspecified"))
      (node (ref "R60") (pin "1") (pinfunction "1_1") (pintype "unspecified"))
    )
    (net (code "166") (name "Net-(LED33-Pad2)") (class "Default")
      (node (ref "LED33") (pin "2") (pinfunction "2_2") (pintype "unspecified"))
      (node (ref "R8") (pin "1") (pinfunction "1_1") (pintype "unspecified"))
    )
    (net (code "167") (name "Net-(LED34-Pad2)") (class "Default")
      (node (ref "LED34") (pin "2") (pinfunction "2_2") (pintype "unspecified"))
      (node (ref "R9") (pin "1") (pinfunction "1_1") (pintype "unspecified"))
    )
    (net (code "168") (name "Net-(LED35-Pad2)") (class "Default")
      (node (ref "LED35") (pin "2") (pinfunction "2_2") (pintype "unspecified"))
      (node (ref "R12") (pin "1") (pinfunction "1_1") (pintype "unspecified"))
    )
    (net (code "169") (name "Net-(LED36-Pad2)") (class "Default")
      (node (ref "LED36") (pin "2") (pinfunction "2_2") (pintype "unspecified"))
      (node (ref "R35") (pin "1") (pinfunction "1_1") (pintype "unspecified"))
    )
    (net (code "170") (name "Net-(LED37-Pad2)") (class "Default")
      (node (ref "LED37") (pin "2") (pinfunction "2_2") (pintype "unspecified"))
      (node (ref "R36") (pin "1") (pinfunction "1_1") (pintype "unspecified"))
    )
    (net (code "171") (name "Net-(LED38-Pad2)") (class "Default")
      (node (ref "LED38") (pin "2") (pinfunction "2_2") (pintype "unspecified"))
      (node (ref "R43") (pin "1") (pinfunction "1_1") (pintype "unspecified"))
    )
    (net (code "172") (name "Net-(LED39-Pad2)") (class "Default")
      (node (ref "LED39") (pin "2") (pinfunction "2_2") (pintype "unspecified"))
      (node (ref "R44") (pin "1") (pinfunction "1_1") (pintype "unspecified"))
    )
    (net (code "173") (name "Net-(LED40-Pad2)") (class "Default")
      (node (ref "LED40") (pin "2") (pinfunction "2_2") (pintype "unspecified"))
      (node (ref "R51") (pin "1") (pinfunction "1_1") (pintype "unspecified"))
    )
    (net (code "174") (name "Net-(LED41-Pad2)") (class "Default")
      (node (ref "LED41") (pin "2") (pinfunction "2_2") (pintype "unspecified"))
      (node (ref "R52") (pin "1") (pinfunction "1_1") (pintype "unspecified"))
    )
    (net (code "175") (name "Net-(LED42-Pad2)") (class "Default")
      (node (ref "LED42") (pin "2") (pinfunction "2_2") (pintype "unspecified"))
      (node (ref "R62") (pin "1") (pinfunction "1_1") (pintype "unspecified"))
    )
    (net (code "176") (name "Net-(LED43-Pad2)") (class "Default")
      (node (ref "LED43") (pin "2") (pinfunction "2_2") (pintype "unspecified"))
      (node (ref "R63") (pin "1") (pinfunction "1_1") (pintype "unspecified"))
    )
    (net (code "177") (name "Net-(LED44-Pad2)") (class "Default")
      (node (ref "LED44") (pin "2") (pinfunction "2_2") (pintype "unspecified"))
      (node (ref "R64") (pin "1") (pinfunction "1_1") (pintype "unspecified"))
    )
    (net (code "178") (name "Net-(LED45-Pad2)") (class "Default")
      (node (ref "LED45") (pin "2") (pinfunction "2_2") (pintype "unspecified"))
      (node (ref "R65") (pin "1") (pinfunction "1_1") (pintype "unspecified"))
    )
    (net (code "179") (name "Net-(LED46-Pad2)") (class "Default")
      (node (ref "LED46") (pin "2") (pinfunction "2_2") (pintype "unspecified"))
      (node (ref "R66") (pin "1") (pinfunction "1_1") (pintype "unspecified"))
    )
    (net (code "180") (name "Net-(LED47-Pad2)") (class "Default")
      (node (ref "LED47") (pin "2") (pinfunction "2_2") (pintype "unspecified"))
      (node (ref "R67") (pin "1") (pinfunction "1_1") (pintype "unspecified"))
    )
    (net (code "181") (name "Net-(LED48-Pad2)") (class "Default")
      (node (ref "LED48") (pin "2") (pinfunction "2_2") (pintype "unspecified"))
      (node (ref "R68") (pin "1") (pinfunction "1_1") (pintype "unspecified"))
    )
    (net (code "182") (name "Net-(LED49-Pad2)") (class "Default")
      (node (ref "LED49") (pin "2") (pinfunction "2_2") (pintype "unspecified"))
      (node (ref "R69") (pin "1") (pinfunction "1_1") (pintype "unspecified"))
    )
    (net (code "183") (name "Net-(LED50-Pad2)") (class "Default")
      (node (ref "LED50") (pin "2") (pinfunction "2_2") (pintype "unspecified"))
      (node (ref "R70") (pin "1") (pinfunction "1_1") (pintype "unspecified"))
    )
    (net (code "184") (name "Net-(LED51-Pad2)") (class "Default")
      (node (ref "LED51") (pin "2") (pinfunction "2_2") (pintype "unspecified"))
      (node (ref "R71") (pin "1") (pinfunction "1_1") (pintype "unspecified"))
    )
    (net (code "185") (name "Net-(LED52-Pad2)") (class "Default")
      (node (ref "LED52") (pin "2") (pinfunction "2_2") (pintype "unspecified"))
      (node (ref "R72") (pin "1") (pinfunction "1_1") (pintype "unspecified"))
    )
    (net (code "186") (name "Net-(LED53-Pad2)") (class "Default")
      (node (ref "LED53") (pin "2") (pinfunction "2_2") (pintype "unspecified"))
      (node (ref "R73") (pin "1") (pinfunction "1_1") (pintype "unspecified"))
    )
    (net (code "187") (name "Net-(LED54-Pad2)") (class "Default")
      (node (ref "LED54") (pin "2") (pinfunction "2_2") (pintype "unspecified"))
      (node (ref "R74") (pin "1") (pinfunction "1_1") (pintype "unspecified"))
    )
    (net (code "188") (name "Net-(LED55-Pad2)") (class "Default")
      (node (ref "LED55") (pin "2") (pinfunction "2_2") (pintype "unspecified"))
      (node (ref "R75") (pin "1") (pinfunction "1_1") (pintype "unspecified"))
    )
    (net (code "189") (name "Net-(LED56-Pad2)") (class "Default")
      (node (ref "LED56") (pin "2") (pinfunction "2_2") (pintype "unspecified"))
      (node (ref "R76") (pin "1") (pinfunction "1_1") (pintype "unspecified"))
    )
    (net (code "190") (name "Net-(REG1-E#)") (class "Default")
      (node (ref "R3") (pin "2") (pinfunction "2_2") (pintype "unspecified"))
      (node (ref "REG1") (pin "1") (pinfunction "E#_1") (pintype "unspecified"))
    )
    (net (code "191") (name "Net-(REG3-E#)") (class "Default")
      (node (ref "R61") (pin "2") (pinfunction "2_2") (pintype "unspecified"))
      (node (ref "REG3") (pin "1") (pinfunction "E#_1") (pintype "unspecified"))
    )
    (net (code "192") (name "Net-(REG5-E#)") (class "Default")
      (node (ref "R78") (pin "2") (pinfunction "2_2") (pintype "unspecified"))
      (node (ref "REG5") (pin "1") (pinfunction "E#_1") (pintype "unspecified"))
    )
    (net (code "193") (name "Net-(REG8-E#)") (class "Default")
      (node (ref "R77") (pin "2") (pinfunction "2_2") (pintype "unspecified"))
      (node (ref "REG8") (pin "1") (pinfunction "E#_1") (pintype "unspecified"))
    )
    (net (code "194") (name "unconnected-(NOR1-A1-Pad2)") (class "Default")
      (node (ref "NOR1") (pin "2") (pinfunction "A1_2") (pintype "unspecified"))
    )
    (net (code "195") (name "unconnected-(NOR1-A2-Pad5)") (class "Default")
      (node (ref "NOR1") (pin "5") (pinfunction "A2_5") (pintype "unspecified"))
    )
    (net (code "196") (name "unconnected-(NOR1-A4-Pad11)") (class "Default")
      (node (ref "NOR1") (pin "11") (pinfunction "A4_11") (pintype "unspecified"))
    )
    (net (code "197") (name "unconnected-(NOR1-B1-Pad3)") (class "Default")
      (node (ref "NOR1") (pin "3") (pinfunction "B1_3") (pintype "unspecified"))
    )
    (net (code "198") (name "unconnected-(NOR1-B2-Pad6)") (class "Default")
      (node (ref "NOR1") (pin "6") (pinfunction "B2_6") (pintype "unspecified"))
    )
    (net (code "199") (name "unconnected-(NOR1-B4-Pad12)") (class "Default")
      (node (ref "NOR1") (pin "12") (pinfunction "B4_12") (pintype "unspecified"))
    )
    (net (code "200") (name "unconnected-(NOR1-Y1-Pad1)") (class "Default")
      (node (ref "NOR1") (pin "1") (pinfunction "Y1_1") (pintype "unspecified"))
    )
    (net (code "201") (name "unconnected-(NOR1-Y2-Pad4)") (class "Default")
      (node (ref "NOR1") (pin "4") (pinfunction "Y2_4") (pintype "unspecified"))
    )
    (net (code "202") (name "unconnected-(NOR1-Y4-Pad13)") (class "Default")
      (node (ref "NOR1") (pin "13") (pinfunction "Y4_13") (pintype "unspecified"))
    )
    (net (code "203") (name "unconnected-(R79-Pad1)") (class "Default")
      (node (ref "R79") (pin "1") (pinfunction "1_1") (pintype "unspecified"))
    )
    (net (code "204") (name "unconnected-(U1-1A-Pad1)") (class "Default")
      (node (ref "U1") (pin "1") (pinfunction "1A_1") (pintype "unspecified"))
    )
    (net (code "205") (name "unconnected-(U1-1B-Pad2)") (class "Default")
      (node (ref "U1") (pin "2") (pinfunction "1B_2") (pintype "unspecified"))
    )
    (net (code "206") (name "unconnected-(U1-1Y-Pad3)") (class "Default")
      (node (ref "U1") (pin "3") (pinfunction "1Y_3") (pintype "unspecified"))
    )
    (net (code "207") (name "unconnected-(U1-2A-Pad4)") (class "Default")
      (node (ref "U1") (pin "4") (pinfunction "2A_4") (pintype "unspecified"))
    )
    (net (code "208") (name "unconnected-(U1-2B-Pad5)") (class "Default")
      (node (ref "U1") (pin "5") (pinfunction "2B_5") (pintype "unspecified"))
    )
    (net (code "209") (name "unconnected-(U1-2Y-Pad6)") (class "Default")
      (node (ref "U1") (pin "6") (pinfunction "2Y_6") (pintype "unspecified"))
    )
    (net (code "210") (name "unconnected-(U1-3A-Pad9)") (class "Default")
      (node (ref "U1") (pin "9") (pinfunction "3A_9") (pintype "unspecified"))
    )
    (net (code "211") (name "unconnected-(U1-3B-Pad10)") (class "Default")
      (node (ref "U1") (pin "10") (pinfunction "3B_10") (pintype "unspecified"))
    )
    (net (code "212") (name "unconnected-(U1-3Y-Pad8)") (class "Default")
      (node (ref "U1") (pin "8") (pinfunction "3Y_8") (pintype "unspecified"))
    )
  )
)
